# loud-esp-mini-rev-f-schematic_easyeda.net
KiCad netlist of a schematic drawn in EasyEDA
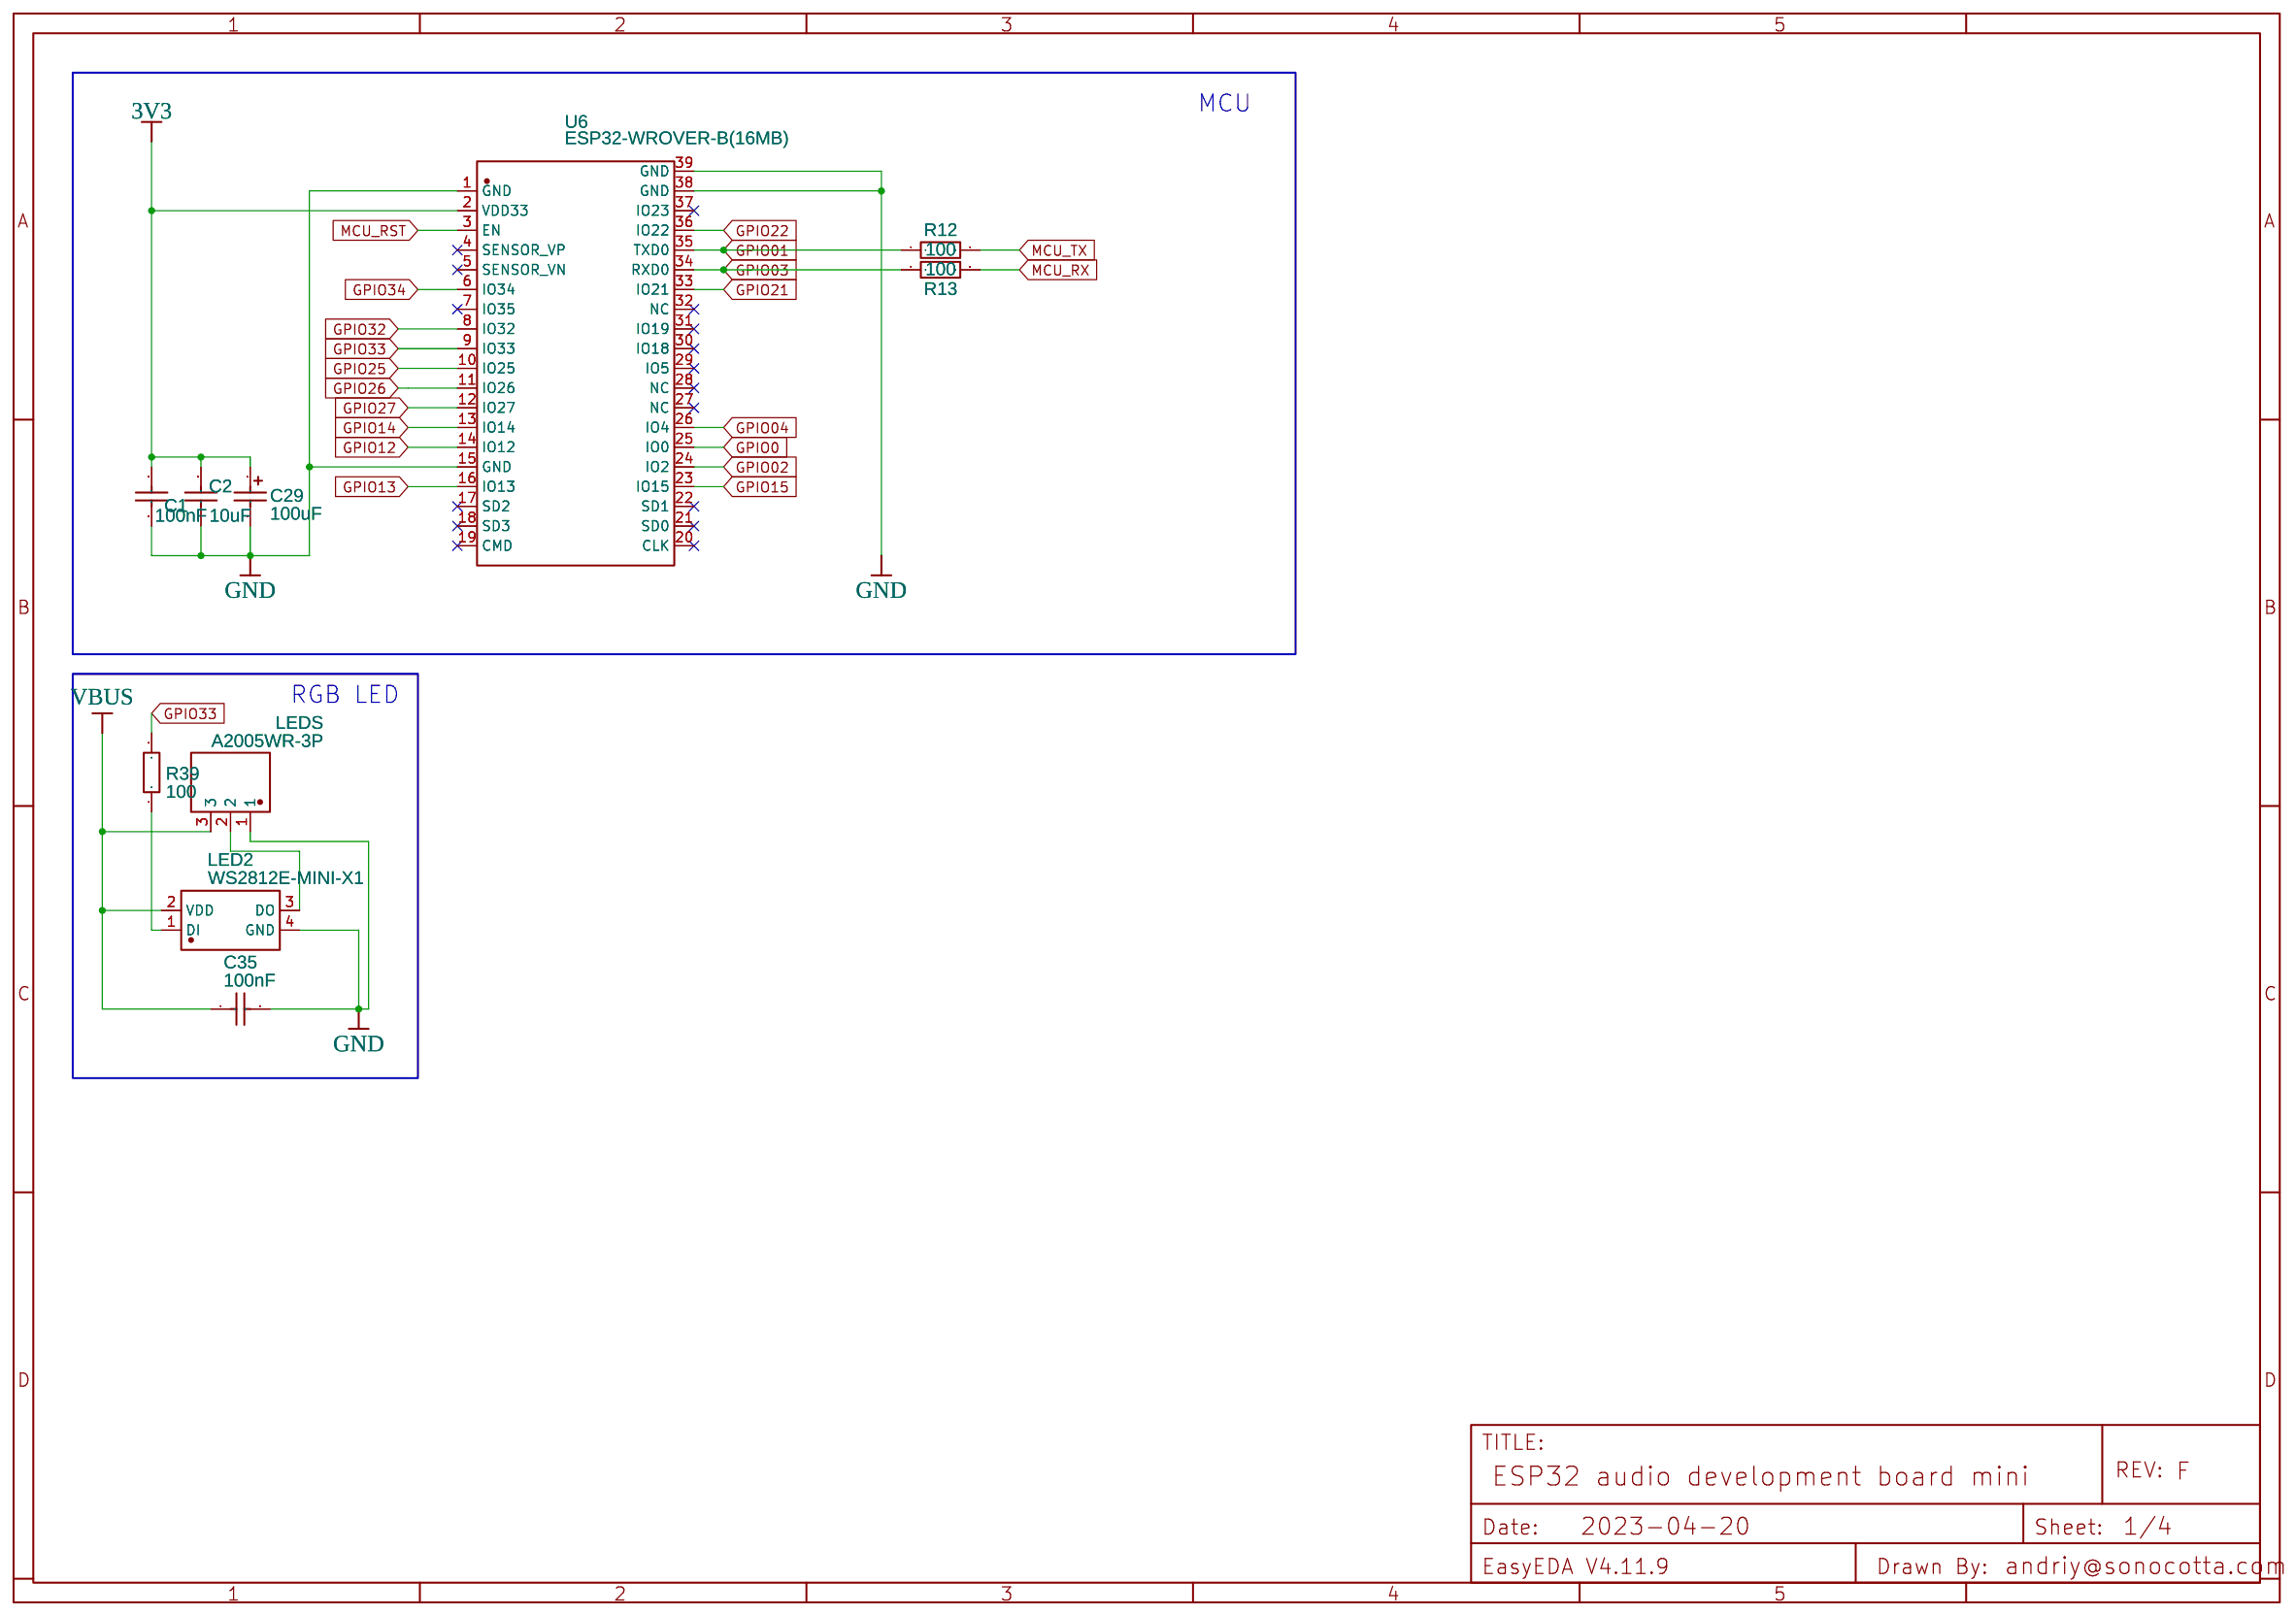
[diagram p0: MCU]
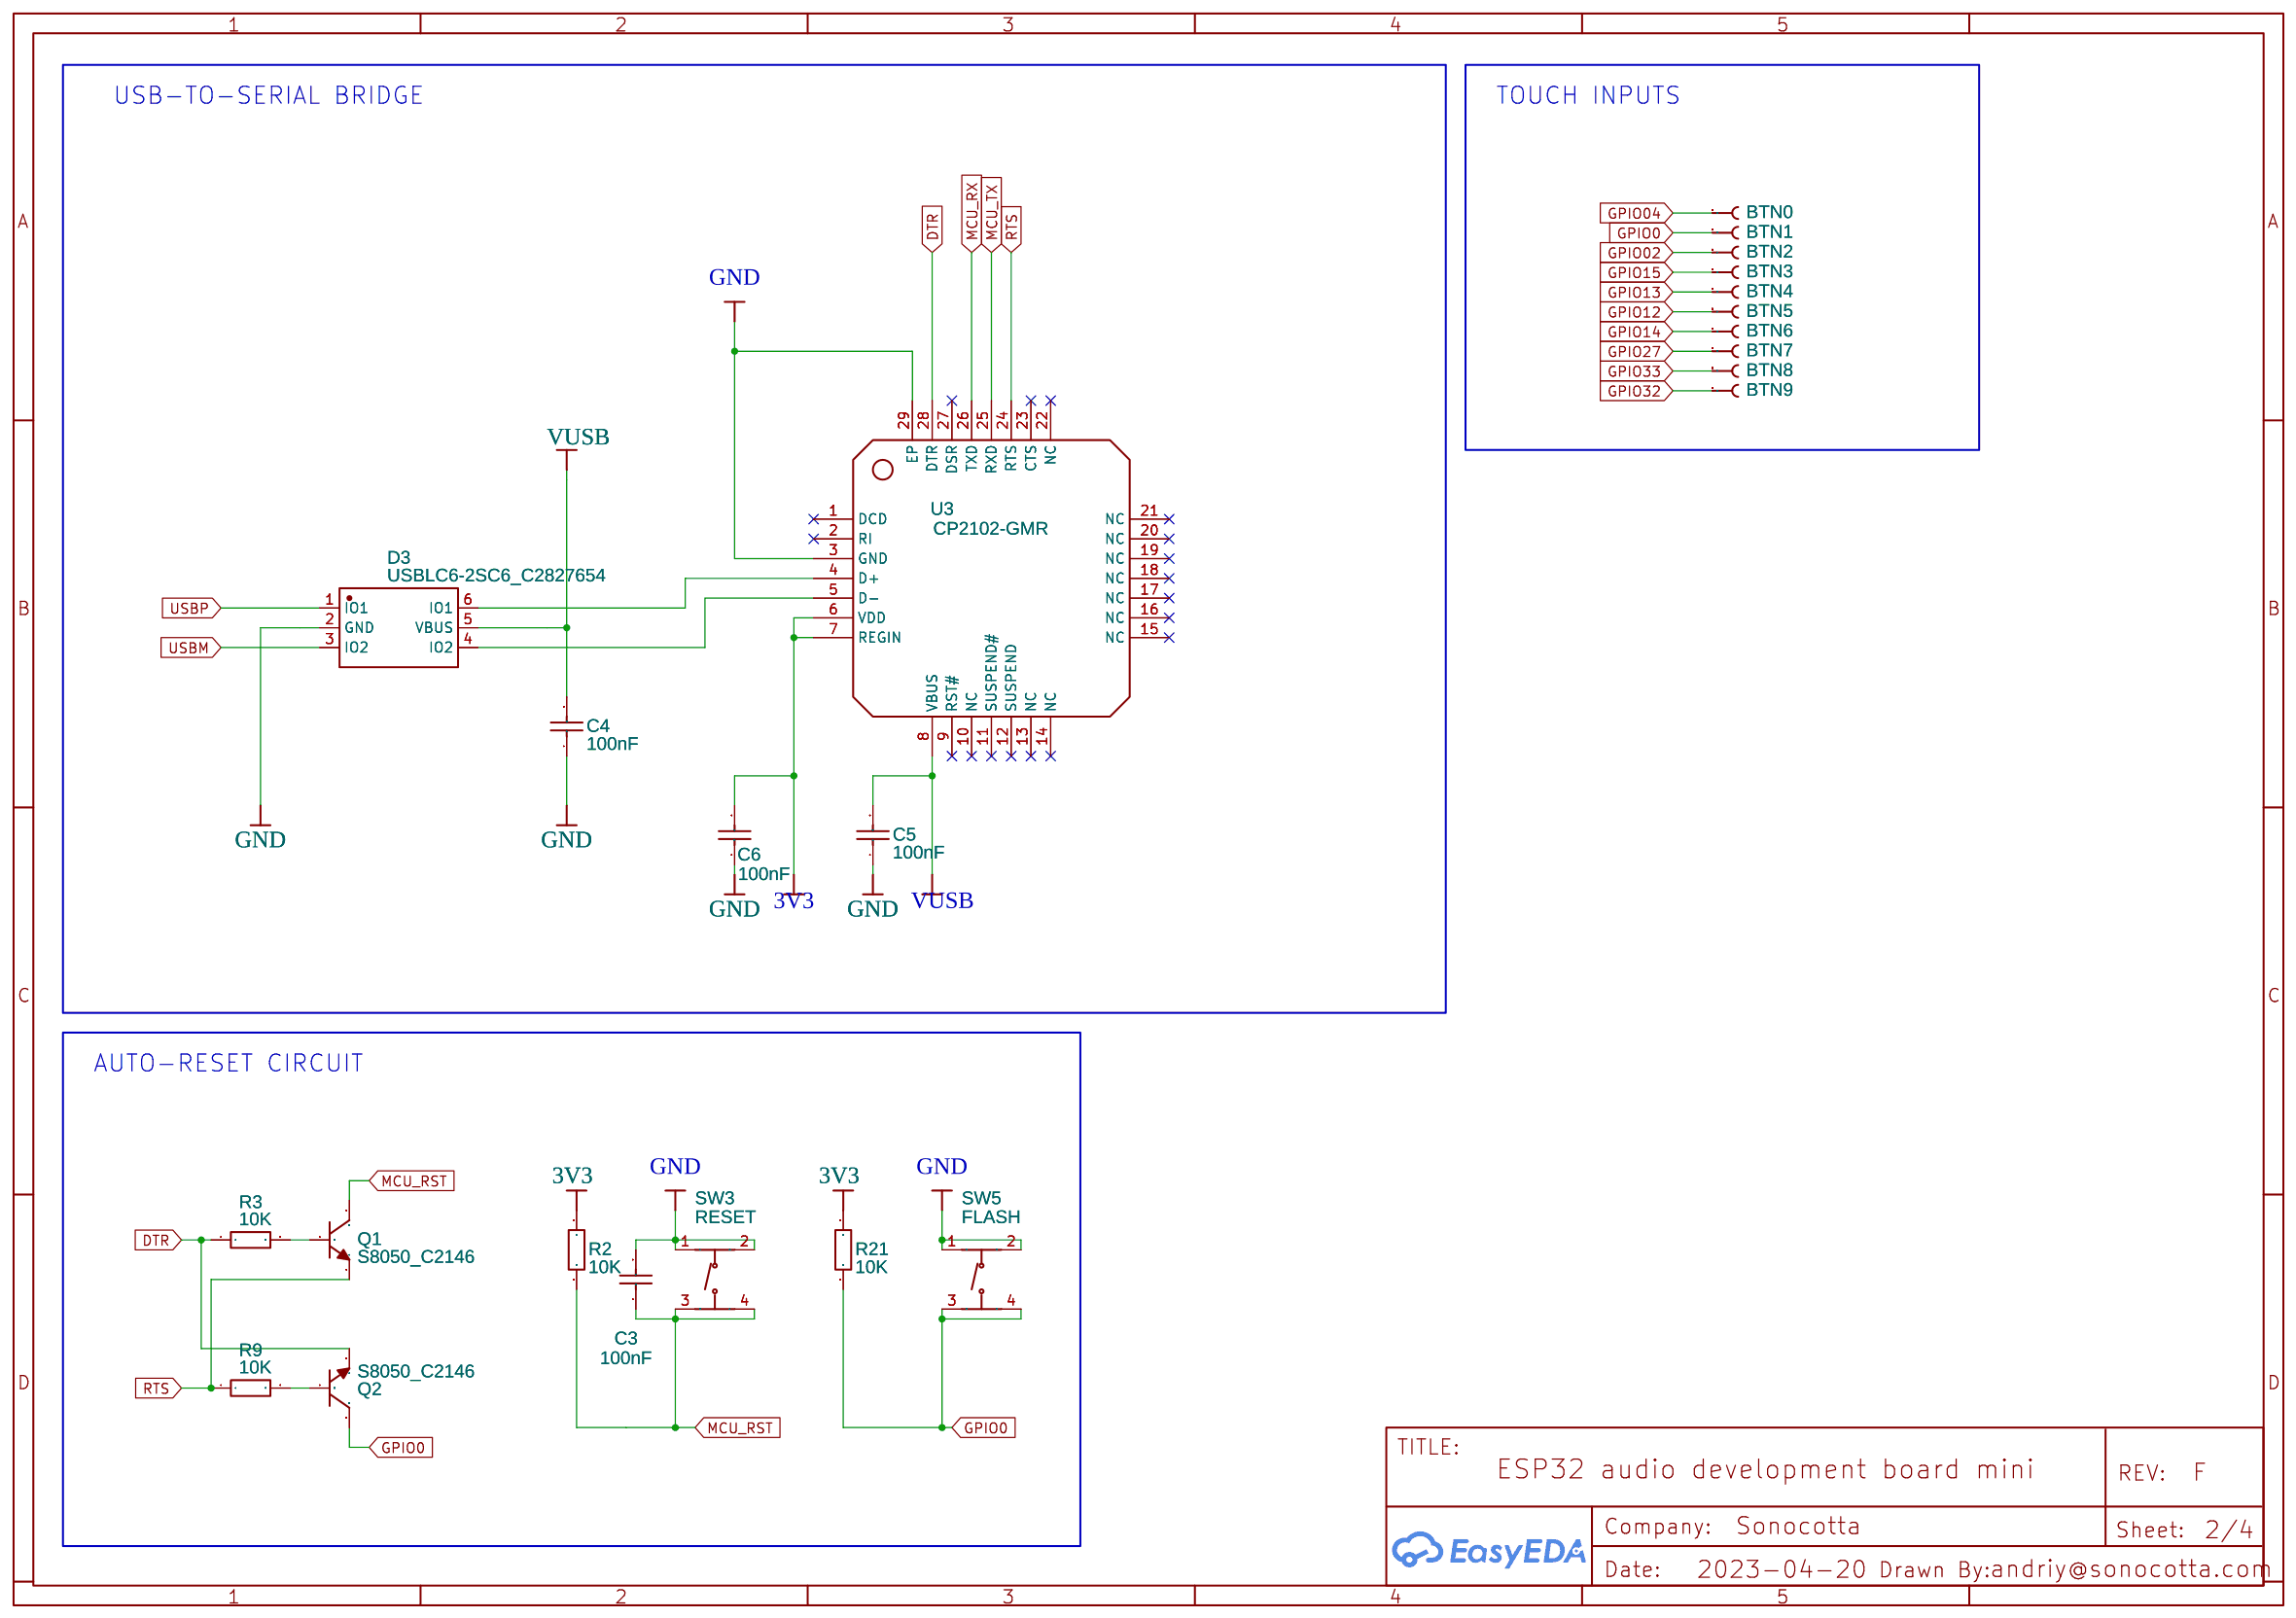
[diagram p1: SERIAL]
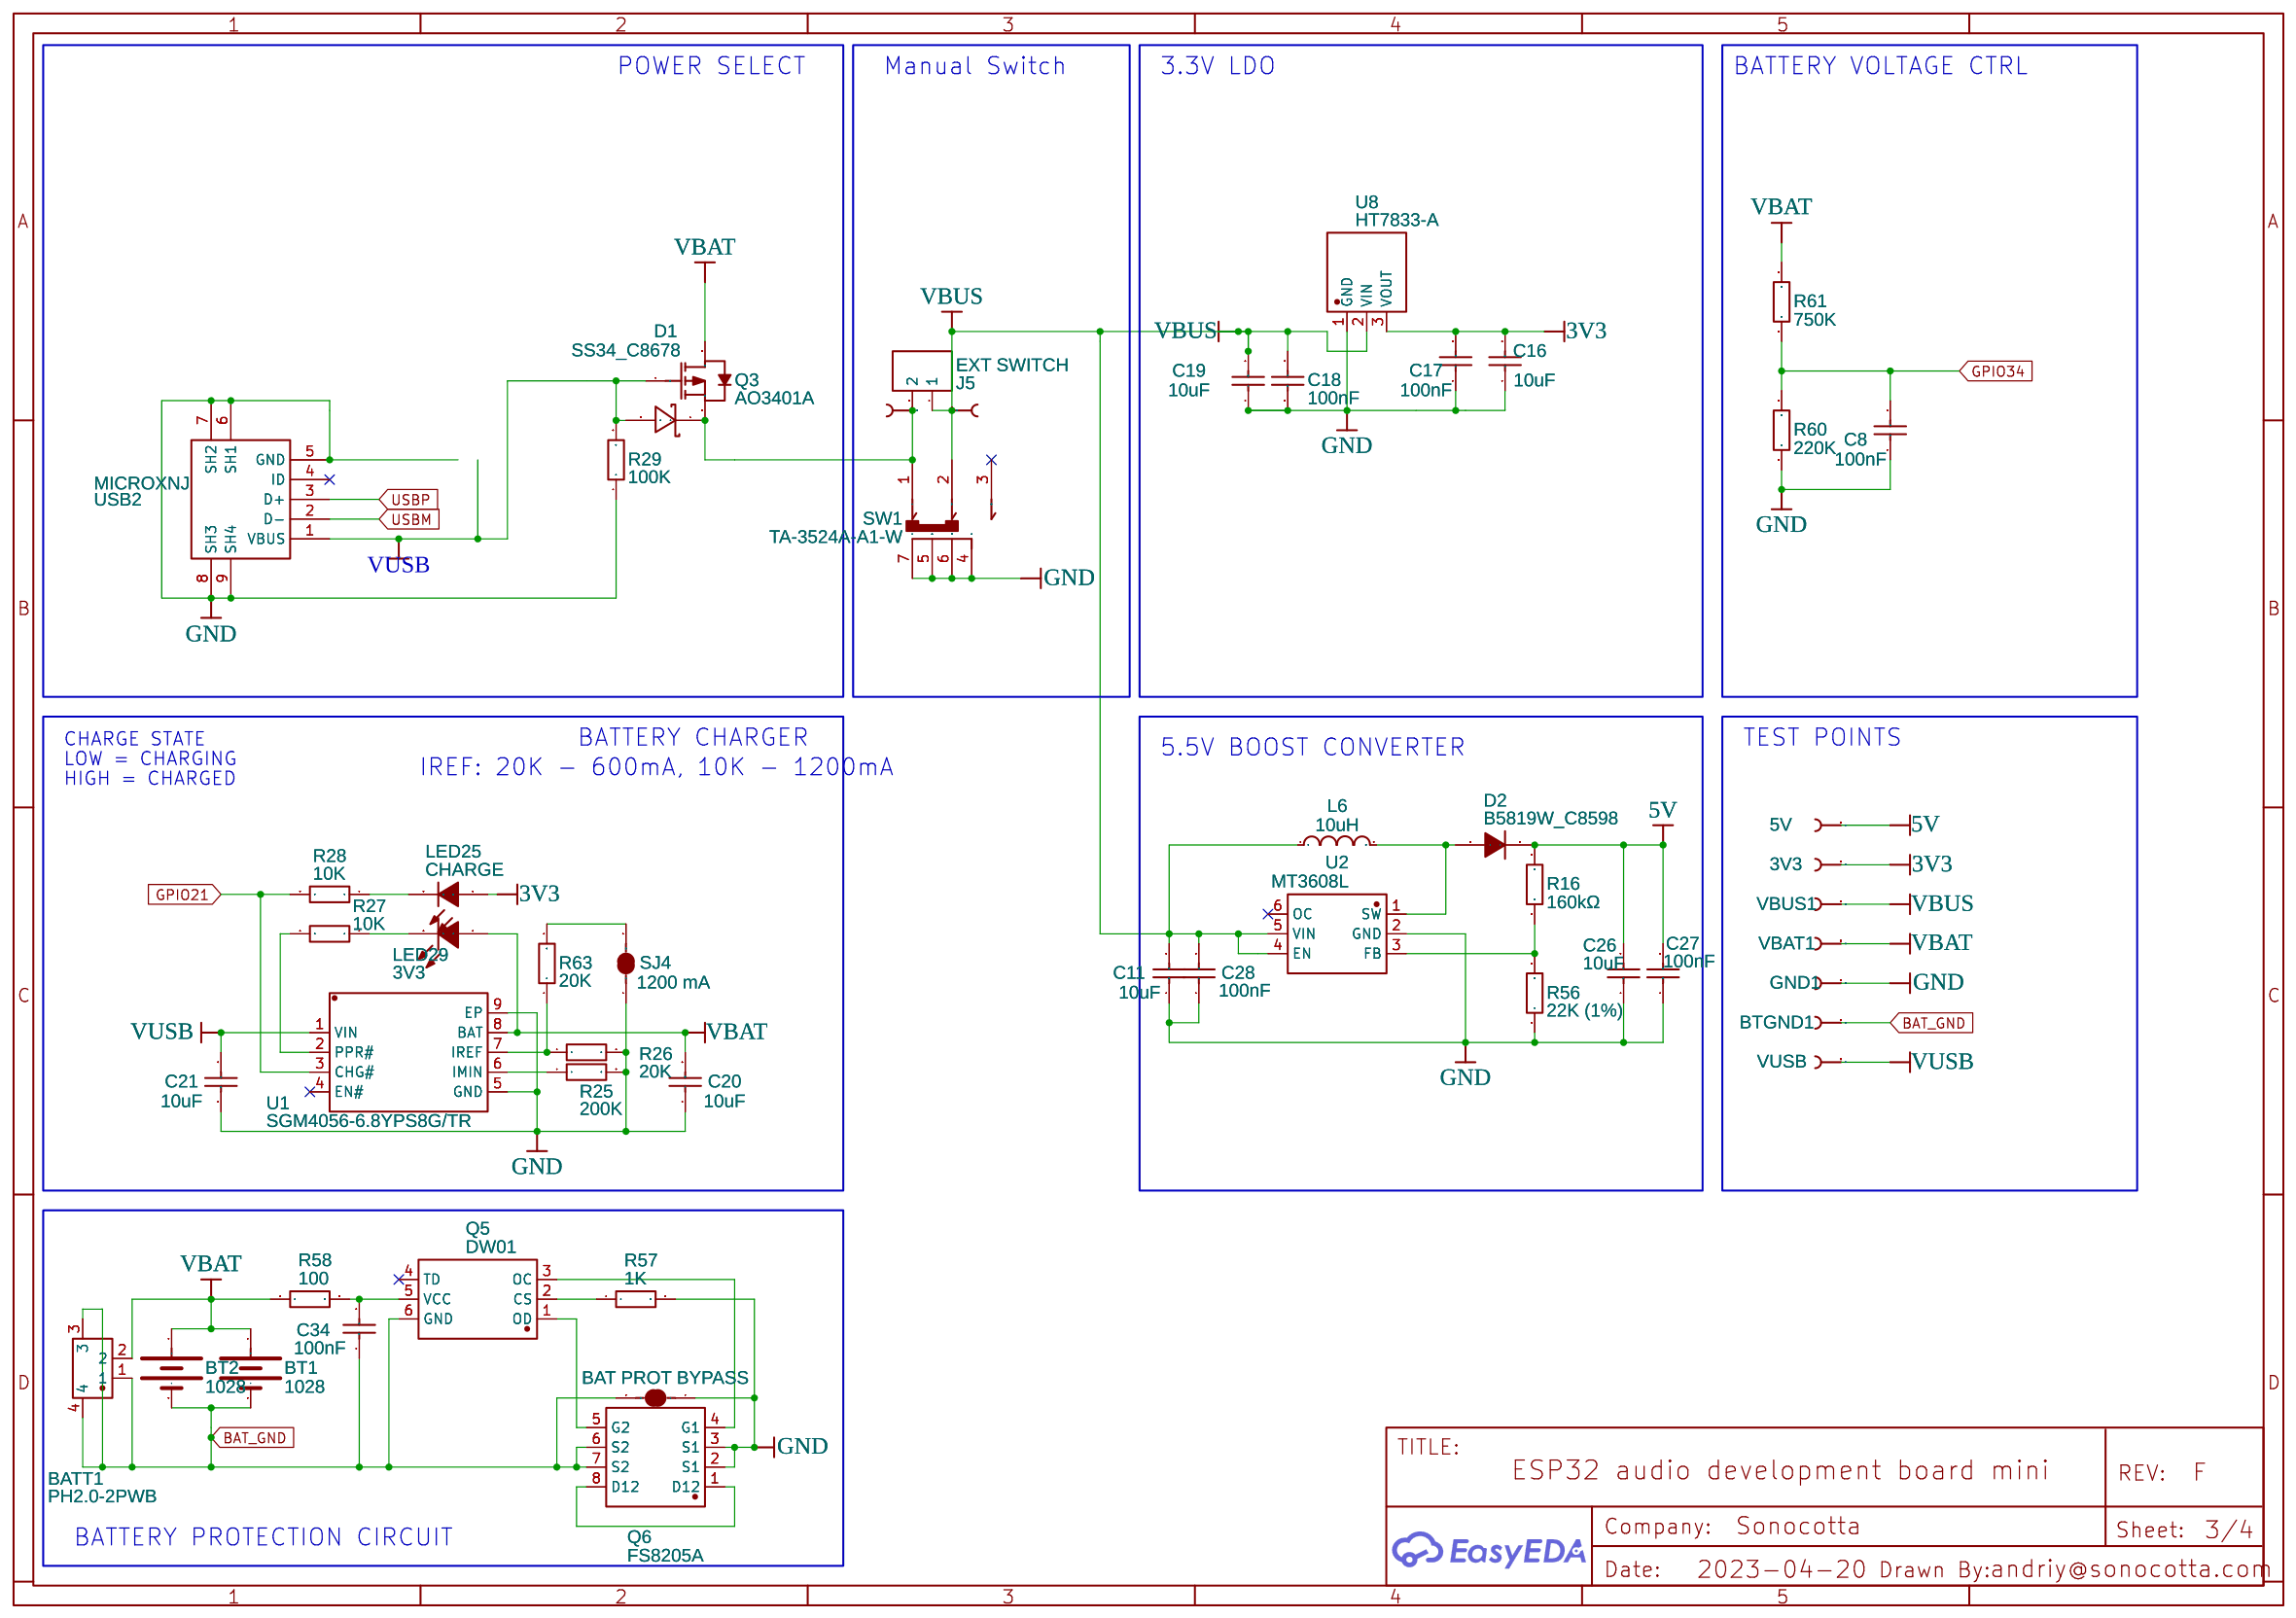
[diagram p2: POWER MGT]
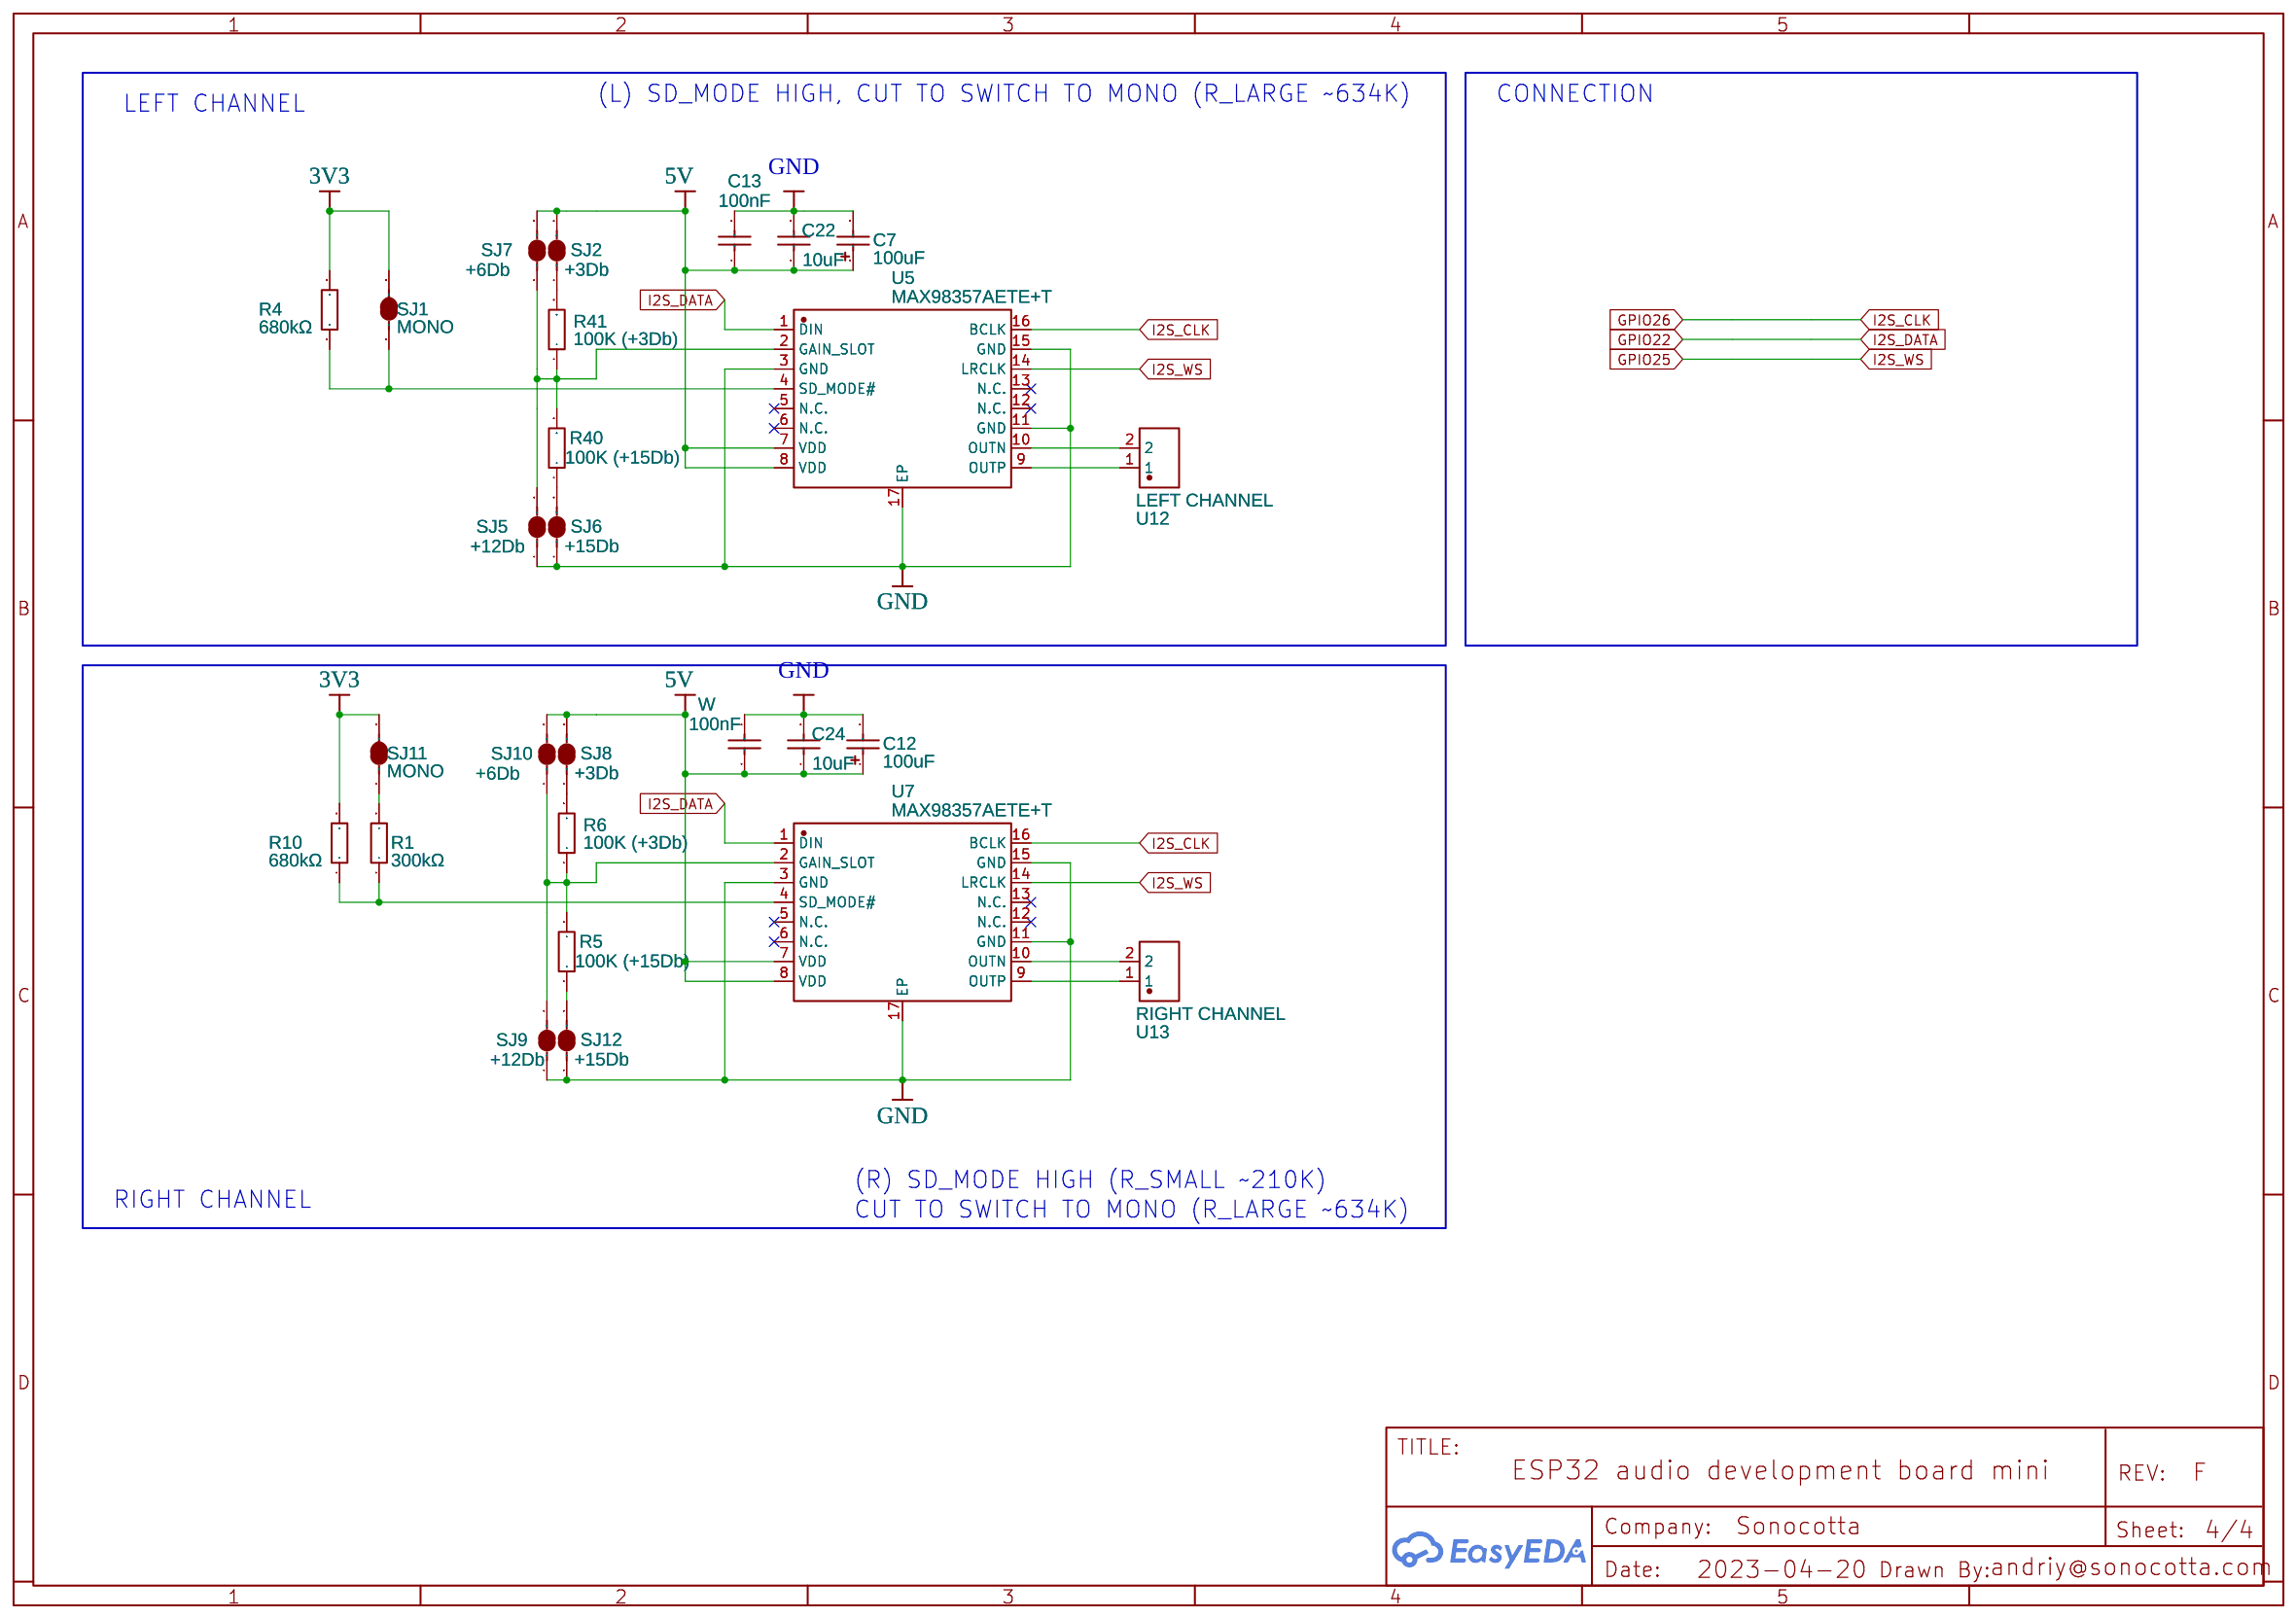
[diagram p3: DAC]

(export (version "E")
  (design (tool "Eeschema 10.0.6"))
  (components
    (comp (ref "C1")
      (value "100nF")
      (fields (field (name "Manufacturer Part") "CL05B104KO5NNNC") (field (name "Manufacturer") "SAMSUNG"))
      (libsource (lib "") (part "CL05B104KO5NNNC"))
    )
    (comp (ref "C2")
      (value "10uF")
      (fields (field (name "Manufacturer Part") "CL21A106KAYNNNE") (field (name "Manufacturer") "SAMSUNG"))
      (libsource (lib "") (part "CL21A106KAYNNNE"))
    )
    (comp (ref "C29")
      (value "100uF")
      (fields (field (name "Manufacturer Part") "TAJB107K006RNJ") (field (name "Manufacturer") "AVX"))
      (libsource (lib "") (part "TAJB107K006RNJ"))
    )
    (comp (ref "C35")
      (value "100nF")
      (fields (field (name "Manufacturer Part") "CL05B104KO5NNNC") (field (name "Manufacturer") "SAMSUNG"))
      (libsource (lib "") (part "C0201X6S104K6R3NTA"))
    )
    (comp (ref "LED2")
      (value "WS2812E-MINI-X1")
      (fields (field (name "Manufacturer") "worldsemi"))
      (libsource (lib "") (part "WS2812E-MINI-X1"))
    )
    (comp (ref "LEDS")
      (value "A2005WR-3P")
      (fields (field (name "Manufacturer") "Changjiang Connectors"))
      (libsource (lib "") (part "A2005WR-3P"))
    )
    (comp (ref "R12")
      (value "100")
      (fields (field (name "Manufacturer Part") "0402WGF1000TCE") (field (name "Manufacturer") "UniOhm"))
      (libsource (lib "") (part "0402WGF1000TCE_1"))
    )
    (comp (ref "R13")
      (value "100")
      (fields (field (name "Manufacturer Part") "0402WGF1000TCE") (field (name "Manufacturer") "UniOhm"))
      (libsource (lib "") (part "0402WGF1000TCE_1"))
    )
    (comp (ref "R39")
      (value "100")
      (fields (field (name "Manufacturer Part") "0402WGF1000TCE") (field (name "Manufacturer") "UniOhm"))
      (libsource (lib "") (part "0402WGF1000TCE"))
    )
    (comp (ref "U6")
      (value "ESP32-WROVER-B(16MB)")
      (fields (field (name "Manufacturer") "Espressif Systems"))
      (libsource (lib "") (part "ESP32-WROVER-B(16MB)"))
    )
    (comp (ref "BTN0") (value "SENSOR CAP 1") (libsource (lib "") (part "TEST-POINT2")))
    (comp (ref "BTN1") (value "SENSOR CAP 1") (libsource (lib "") (part "TEST-POINT2")))
    (comp (ref "BTN2") (value "SENSOR CAP 1") (libsource (lib "") (part "TEST-POINT2")))
    (comp (ref "BTN3") (value "SENSOR CAP 1") (libsource (lib "") (part "TEST-POINT2")))
    (comp (ref "BTN4") (value "SENSOR CAP 1") (libsource (lib "") (part "TEST-POINT2")))
    (comp (ref "BTN5") (value "SENSOR CAP 1") (libsource (lib "") (part "TEST-POINT2")))
    (comp (ref "BTN6") (value "SENSOR CAP 1") (libsource (lib "") (part "TEST-POINT2")))
    (comp (ref "BTN7") (value "SENSOR CAP 1") (libsource (lib "") (part "TEST-POINT2")))
    (comp (ref "BTN8") (value "SENSOR CAP 1") (libsource (lib "") (part "TEST-POINT2")))
    (comp (ref "BTN9") (value "SENSOR CAP 1") (libsource (lib "") (part "TEST-POINT2")))
    (comp (ref "C3")
      (value "100nF")
      (fields
        (field (name "BOM_Manufacturer Part") "CL05B104KO5NNNC")
        (field (name "BOM_Supplier Part") "C1525")
      )
      (libsource (lib "") (part "CL05B104KO5NNNC"))
    )
    (comp (ref "C4")
      (value "100nF")
      (fields
        (field (name "BOM_Manufacturer Part") "CL05B104KO5NNNC")
        (field (name "BOM_Supplier Part") "C1525")
      )
      (libsource (lib "") (part "CL05B104KO5NNNC"))
    )
    (comp (ref "C5")
      (value "100nF")
      (fields
        (field (name "BOM_Manufacturer Part") "CL05B104KO5NNNC")
        (field (name "BOM_Supplier Part") "C1525")
      )
      (libsource (lib "") (part "CL05B104KO5NNNC"))
    )
    (comp (ref "C6")
      (value "100nF")
      (fields
        (field (name "BOM_Manufacturer Part") "CL05B104KO5NNNC")
        (field (name "BOM_Supplier Part") "C1525")
      )
      (libsource (lib "") (part "CL05B104KO5NNNC"))
    )
    (comp (ref "D3")
      (value "USBLC6-2SC6_C2827654")
      (fields
        (field (name "BOM_Manufacturer Part") "USBLC6-2SC6")
        (field (name "BOM_Supplier Part") "C2827654")
      )
      (libsource (lib "") (part "USBLC6-2SC6_C2827654"))
    )
    (comp (ref "Q1")
      (value "S8050_C2146")
      (fields (field (name "BOM_Manufacturer Part") "S8050") (field (name "BOM_Supplier Part") "C2146"))
      (libsource (lib "") (part "S8050_C2146_1"))
    )
    (comp (ref "Q2")
      (value "S8050_C2146")
      (fields (field (name "BOM_Manufacturer Part") "S8050") (field (name "BOM_Supplier Part") "C2146"))
      (libsource (lib "") (part "S8050_C2146"))
    )
    (comp (ref "R2")
      (value "10K")
      (fields
        (field (name "BOM_Manufacturer Part") "0402WGF1002TCE")
        (field (name "BOM_Supplier Part") "C25744")
      )
      (libsource (lib "") (part "0402WGF1002TCE"))
    )
    (comp (ref "R3")
      (value "10K")
      (fields
        (field (name "BOM_Manufacturer Part") "0402WGF1002TCE")
        (field (name "BOM_Supplier Part") "C25744")
      )
      (libsource (lib "") (part "0402WGF1002TCE_1"))
    )
    (comp (ref "R9")
      (value "10K")
      (fields
        (field (name "BOM_Manufacturer Part") "0402WGF1002TCE")
        (field (name "BOM_Supplier Part") "C25744")
      )
      (libsource (lib "") (part "0402WGF1002TCE_1"))
    )
    (comp (ref "R21")
      (value "10K")
      (fields
        (field (name "BOM_Manufacturer Part") "0402WGF1002TCE")
        (field (name "BOM_Supplier Part") "C25744")
      )
      (libsource (lib "") (part "0402WGF1002TCE"))
    )
    (comp (ref "SW3")
      (value "RESET")
      (fields
        (field (name "BOM_Manufacturer Part") "TS-1187A-B-A-B")
        (field (name "BOM_Supplier Part") "C318884")
      )
      (libsource (lib "") (part "TS-1187A-B-A-B"))
    )
    (comp (ref "SW5")
      (value "FLASH")
      (fields
        (field (name "BOM_Manufacturer Part") "TS-1187A-B-A-B")
        (field (name "BOM_Supplier Part") "C318884")
      )
      (libsource (lib "") (part "TS-1187A-B-A-B"))
    )
    (comp (ref "U3")
      (value "CP2102-GMR")
      (fields (field (name "BOM_Supplier Part") "C6568"))
      (libsource (lib "") (part "CP2102-GMR"))
    )
    (comp (ref "3V3") (value "SENSOR CAP 1") (libsource (lib "") (part "TEST-POINT2_3")))
    (comp (ref "5V") (value "SENSOR CAP 1") (libsource (lib "") (part "TEST-POINT2_6")))
    (comp (ref "BATT1")
      (value "PH2.0-2PWB")
      (fields
        (field (name "BOM_Manufacturer Part") "PH2.0-2PWB Horizontal")
        (field (name "BOM_Supplier Part") "C47647")
      )
      (libsource (lib "") (part "PH2.0-2PWB"))
    )
    (comp (ref "BT1")
      (value "1028")
      (fields (field (name "BOM_Supplier Part") "C238063"))
      (libsource (lib "") (part "1028"))
    )
    (comp (ref "BT2")
      (value "1028")
      (fields (field (name "BOM_Supplier Part") "C238063"))
      (libsource (lib "") (part "1028"))
    )
    (comp (ref "BTGND1") (value "SENSOR CAP 1") (libsource (lib "") (part "TEST-POINT2_4")))
    (comp (ref "C8")
      (value "100nF")
      (fields
        (field (name "BOM_Manufacturer Part") "CL05B104KO5NNNC")
        (field (name "BOM_Supplier Part") "C1525")
      )
      (libsource (lib "") (part "CL05B104KO5NNNC"))
    )
    (comp (ref "C11")
      (value "10uF")
      (fields
        (field (name "BOM_Manufacturer Part") "CL21A106KAYNNNE")
        (field (name "BOM_Supplier Part") "C15850")
      )
      (libsource (lib "") (part "CL21A106KAYNNNE"))
    )
    (comp (ref "C16")
      (value "10uF")
      (fields
        (field (name "BOM_Manufacturer Part") "CL21A106KAYNNNE")
        (field (name "BOM_Supplier Part") "C15850")
      )
      (libsource (lib "") (part "CL21A106KAYNNNE"))
    )
    (comp (ref "C17")
      (value "100nF")
      (fields
        (field (name "BOM_Manufacturer Part") "CL05B104KO5NNNC")
        (field (name "BOM_Supplier Part") "C1525")
      )
      (libsource (lib "") (part "CL05B104KO5NNNC"))
    )
    (comp (ref "C18")
      (value "100nF")
      (fields
        (field (name "BOM_Manufacturer Part") "CL05B104KO5NNNC")
        (field (name "BOM_Supplier Part") "C1525")
      )
      (libsource (lib "") (part "CL05B104KO5NNNC"))
    )
    (comp (ref "C19")
      (value "10uF")
      (fields
        (field (name "BOM_Manufacturer Part") "CL21A106KAYNNNE")
        (field (name "BOM_Supplier Part") "C15850")
      )
      (libsource (lib "") (part "CL21A106KAYNNNE"))
    )
    (comp (ref "C20")
      (value "10uF")
      (fields
        (field (name "BOM_Manufacturer Part") "CL21A106KAYNNNE")
        (field (name "BOM_Supplier Part") "C15850")
      )
      (libsource (lib "") (part "CL21A106KAYNNNE"))
    )
    (comp (ref "C21")
      (value "10uF")
      (fields
        (field (name "BOM_Manufacturer Part") "CL21A106KAYNNNE")
        (field (name "BOM_Supplier Part") "C15850")
      )
      (libsource (lib "") (part "CL21A106KAYNNNE"))
    )
    (comp (ref "C26")
      (value "10uF")
      (fields
        (field (name "BOM_Manufacturer Part") "CL21A106KAYNNNE")
        (field (name "BOM_Supplier Part") "C15850")
      )
      (libsource (lib "") (part "CL21A106KAYNNNE"))
    )
    (comp (ref "C27")
      (value "100nF")
      (fields
        (field (name "BOM_Manufacturer Part") "CL05B104KO5NNNC")
        (field (name "BOM_Supplier Part") "C1525")
      )
      (libsource (lib "") (part "CL05B104KO5NNNC"))
    )
    (comp (ref "C28")
      (value "100nF")
      (fields
        (field (name "BOM_Manufacturer Part") "CL05B104KO5NNNC")
        (field (name "BOM_Supplier Part") "C1525")
      )
      (libsource (lib "") (part "CL05B104KO5NNNC"))
    )
    (comp (ref "C34")
      (value "100nF")
      (fields
        (field (name "BOM_Manufacturer Part") "CL05B104KO5NNNC")
        (field (name "BOM_Supplier Part") "C1525")
      )
      (libsource (lib "") (part "CL05B104KO5NNNC"))
    )
    (comp (ref "D1")
      (value "SS34_C8678")
      (fields (field (name "BOM_Manufacturer Part") "SS34") (field (name "BOM_Supplier Part") "C8678"))
      (libsource (lib "") (part "SS34_C8678"))
    )
    (comp (ref "D2")
      (value "B5819W_C8598")
      (fields (field (name "BOM_Manufacturer Part") "B5819W") (field (name "BOM_Supplier Part") "C8598"))
      (libsource (lib "") (part "B5819W_C8598"))
    )
    (comp (ref "EXT_SW_1") (value "SENSOR CAP 1") (libsource (lib "") (part "TEST-POINT2_7")))
    (comp (ref "EXT_SW_2") (value "SENSOR CAP 1") (libsource (lib "") (part "TEST-POINT2")))
    (comp (ref "GND1") (value "SENSOR CAP 1") (libsource (lib "") (part "TEST-POINT2_1")))
    (comp (ref "J5")
      (value "EXT SWITCH")
      (fields (field (name "BOM_Supplier Part") "C124375"))
      (libsource (lib "") (part "HDR-M-2.54_1x2"))
    )
    (comp (ref "L6")
      (value "10uH")
      (fields
        (field (name "BOM_Manufacturer Part") "FXL0630-100-M")
        (field (name "BOM_Supplier Part") "C167223")
      )
      (libsource (lib "") (part "FXL0630-100-M"))
    )
    (comp (ref "LED25")
      (value "CHARGE")
      (fields
        (field (name "BOM_Manufacturer Part") "19-217/GHC-YR1S2/3T")
        (field (name "BOM_Supplier Part") "C72043")
      )
      (libsource (lib "") (part "19-217/GHC-YR1S2/3T"))
    )
    (comp (ref "LED29")
      (value "3V3")
      (fields (field (name "BOM_Manufacturer Part") "KT-0603R") (field (name "BOM_Supplier Part") "C2286"))
      (libsource (lib "") (part "KT-0603R"))
    )
    (comp (ref "Q3")
      (value "AO3401A")
      (fields (field (name "BOM_Supplier Part") "C15127"))
      (libsource (lib "") (part "AO3401A"))
    )
    (comp (ref "Q5")
      (value "DW01")
      (fields (field (name "BOM_Supplier Part") "C181096"))
      (libsource (lib "") (part "DW01"))
    )
    (comp (ref "Q6")
      (value "FS8205A")
      (fields (field (name "BOM_Supplier Part") "C16052"))
      (libsource (lib "") (part "FS8205A"))
    )
    (comp (ref "R16")
      (value "160kΩ")
      (fields
        (field (name "BOM_Manufacturer Part") "0603WAF1603T5E")
        (field (name "BOM_Supplier Part") "C22813")
      )
      (libsource (lib "") (part "0603WAF1603T5E"))
    )
    (comp (ref "R25")
      (value "200K")
      (fields
        (field (name "BOM_Manufacturer Part") "0402WGF2003TCE")
        (field (name "BOM_Supplier Part") "C25764")
      )
      (libsource (lib "") (part "0402WGF2003TCE"))
    )
    (comp (ref "R26")
      (value "20K")
      (fields
        (field (name "BOM_Manufacturer Part") "0402WGF2002TCE")
        (field (name "BOM_Supplier Part") "C25765")
      )
      (libsource (lib "") (part "0402WGF2002TCE_1"))
    )
    (comp (ref "R27")
      (value "10K")
      (fields
        (field (name "BOM_Manufacturer Part") "0402WGF1002TCE")
        (field (name "BOM_Supplier Part") "C25744")
      )
      (libsource (lib "") (part "0402WGF1002TCE"))
    )
    (comp (ref "R28")
      (value "10K")
      (fields
        (field (name "BOM_Manufacturer Part") "0402WGF1002TCE")
        (field (name "BOM_Supplier Part") "C25744")
      )
      (libsource (lib "") (part "0402WGF1002TCE"))
    )
    (comp (ref "R29")
      (value "100K")
      (fields
        (field (name "BOM_Manufacturer Part") "0402WGF1003TCE")
        (field (name "BOM_Supplier Part") "C25741")
      )
      (libsource (lib "") (part "0402WGF1003TCE"))
    )
    (comp (ref "R56")
      (value "22K (1%)")
      (fields
        (field (name "BOM_Manufacturer Part") "0603WAF2202T5E")
        (field (name "BOM_Supplier Part") "C31850")
      )
      (libsource (lib "") (part "0603WAF2202T5E"))
    )
    (comp (ref "R57")
      (value "1K")
      (fields
        (field (name "BOM_Manufacturer Part") "0402WGF1001TCE")
        (field (name "BOM_Supplier Part") "C11702")
      )
      (libsource (lib "") (part "0402WGF1001TCE"))
    )
    (comp (ref "R58")
      (value "100")
      (fields
        (field (name "BOM_Manufacturer Part") "0402WGF1000TCE")
        (field (name "BOM_Supplier Part") "C25076")
      )
      (libsource (lib "") (part "0402WGF1000TCE"))
    )
    (comp (ref "R60")
      (value "220K")
      (fields
        (field (name "BOM_Manufacturer Part") "0603WAF2203T5E")
        (field (name "BOM_Supplier Part") "C22961")
      )
      (libsource (lib "") (part "0603WAF2203T5E"))
    )
    (comp (ref "R61")
      (value "750K")
      (fields
        (field (name "BOM_Manufacturer Part") "0603WAF7503T5E")
        (field (name "BOM_Supplier Part") "C23240")
      )
      (libsource (lib "") (part "0603WAF7503T5E"))
    )
    (comp (ref "R63")
      (value "20K")
      (fields
        (field (name "BOM_Manufacturer Part") "0402WGF2002TCE")
        (field (name "BOM_Supplier Part") "C25765")
      )
      (libsource (lib "") (part "0402WGF2002TCE"))
    )
    (comp (ref "SJ3") (value "BAT PROT BYPASS") (libsource (lib "") (part "JUMPER-PAD-2-NO")))
    (comp (ref "SJ4") (value "1200 mA") (libsource (lib "") (part "JUMPER-PAD-2-NO_1")))
    (comp (ref "SW1")
      (value "TA-3524A-A1-W")
      (fields (field (name "BOM_Supplier Part") "C730329"))
      (libsource (lib "") (part "TA-3524A-A1-W"))
    )
    (comp (ref "U1")
      (value "SGM4056-6.8YPS8G/TR")
      (fields (field (name "BOM_Supplier Part") "C79687"))
      (libsource (lib "") (part "SGM4056-6.8YPS8G/TR"))
    )
    (comp (ref "U2")
      (value "MT3608L")
      (fields (field (name "BOM_Supplier Part") "C2932326"))
      (libsource (lib "") (part "MT3608L"))
    )
    (comp (ref "U8")
      (value "HT7833-A")
      (fields (field (name "BOM_Supplier Part") "C347195"))
      (libsource (lib "") (part "HT7833-A"))
    )
    (comp (ref "USB2")
      (value "MICROXNJ")
      (fields (field (name "BOM_Manufacturer Part") "MicroXNJ") (field (name "BOM_Supplier Part") "C404969"))
      (libsource (lib "") (part "MICROXNJ"))
    )
    (comp (ref "VBAT1") (value "SENSOR CAP 1") (libsource (lib "") (part "TEST-POINT2_2")))
    (comp (ref "VBUS1") (value "SENSOR CAP 1") (libsource (lib "") (part "TEST-POINT2_8")))
    (comp (ref "VUSB") (value "SENSOR CAP 1") (libsource (lib "") (part "TEST-POINT2_5")))
    (comp (ref "C7")
      (value "100uF")
      (fields
        (field (name "BOM_Manufacturer Part") "TAJB107K006RNJ")
        (field (name "BOM_Supplier Part") "C16133")
      )
      (libsource (lib "") (part "TAJB107K006RNJ"))
    )
    (comp (ref "C12")
      (value "100uF")
      (fields
        (field (name "BOM_Manufacturer Part") "TAJB107K006RNJ")
        (field (name "BOM_Supplier Part") "C16133")
      )
      (libsource (lib "") (part "TAJB107K006RNJ"))
    )
    (comp (ref "C13")
      (value "100nF")
      (fields
        (field (name "BOM_Manufacturer Part") "CL05B104KO5NNNC")
        (field (name "BOM_Supplier Part") "C1525")
      )
      (libsource (lib "") (part "CL05B104KO5NNNC"))
    )
    (comp (ref "C22")
      (value "10uF")
      (fields
        (field (name "BOM_Manufacturer Part") "CL21A106KAYNNNE")
        (field (name "BOM_Supplier Part") "C15850")
      )
      (libsource (lib "") (part "CL21A106KAYNNNE"))
    )
    (comp (ref "C24")
      (value "10uF")
      (fields
        (field (name "BOM_Manufacturer Part") "CL21A106KAYNNNE")
        (field (name "BOM_Supplier Part") "C15850")
      )
      (libsource (lib "") (part "CL21A106KAYNNNE"))
    )
    (comp (ref "R1")
      (value "300kΩ")
      (fields
        (field (name "BOM_Manufacturer Part") "0402WGF3003TCE")
        (field (name "BOM_Supplier Part") "C25774")
      )
      (libsource (lib "") (part "0402WGF3003TCE"))
    )
    (comp (ref "R4")
      (value "680kΩ")
      (fields
        (field (name "BOM_Manufacturer Part") "0603WAF6803T5E")
        (field (name "BOM_Supplier Part") "C25822")
      )
      (libsource (lib "") (part "0603WAF6803T5E"))
    )
    (comp (ref "R5")
      (value "100K (+15Db)")
      (fields
        (field (name "BOM_Manufacturer Part") "0402WGF1003TCE")
        (field (name "BOM_Supplier Part") "C25741")
      )
      (libsource (lib "") (part "0402WGF1003TCE"))
    )
    (comp (ref "R6")
      (value "100K (+3Db)")
      (fields
        (field (name "BOM_Manufacturer Part") "0402WGF1003TCE")
        (field (name "BOM_Supplier Part") "C25741")
      )
      (libsource (lib "") (part "0402WGF1003TCE"))
    )
    (comp (ref "R10")
      (value "680kΩ")
      (fields
        (field (name "BOM_Manufacturer Part") "0603WAF6803T5E")
        (field (name "BOM_Supplier Part") "C25822")
      )
      (libsource (lib "") (part "0603WAF6803T5E"))
    )
    (comp (ref "R40")
      (value "100K (+15Db)")
      (fields
        (field (name "BOM_Manufacturer Part") "0402WGF1003TCE")
        (field (name "BOM_Supplier Part") "C25741")
      )
      (libsource (lib "") (part "0402WGF1003TCE"))
    )
    (comp (ref "R41")
      (value "100K (+3Db)")
      (fields
        (field (name "BOM_Manufacturer Part") "0402WGF1003TCE")
        (field (name "BOM_Supplier Part") "C25741")
      )
      (libsource (lib "") (part "0402WGF1003TCE"))
    )
    (comp (ref "SJ1") (value "MONO") (libsource (lib "") (part "JUMPER-PAD-2-NC_BY_TRACENO_SILK")))
    (comp (ref "SJ2") (value "+3Db") (libsource (lib "") (part "JUMPER-PAD-2-NO")))
    (comp (ref "SJ5") (value "+12Db") (libsource (lib "") (part "JUMPER-PAD-2-NO")))
    (comp (ref "SJ6") (value "+15Db") (libsource (lib "") (part "JUMPER-PAD-2-NO")))
    (comp (ref "SJ7") (value "+6Db") (libsource (lib "") (part "JUMPER-PAD-2-NO")))
    (comp (ref "SJ8") (value "+3Db") (libsource (lib "") (part "JUMPER-PAD-2-NO")))
    (comp (ref "SJ9") (value "+12Db") (libsource (lib "") (part "JUMPER-PAD-2-NO")))
    (comp (ref "SJ10") (value "+6Db") (libsource (lib "") (part "JUMPER-PAD-2-NO")))
    (comp (ref "SJ11") (value "MONO") (libsource (lib "") (part "JUMPER-PAD-2-NC_BY_TRACENO_SILK")))
    (comp (ref "SJ12") (value "+15Db") (libsource (lib "") (part "JUMPER-PAD-2-NO")))
    (comp (ref "U5")
      (value "MAX98357AETE+T")
      (fields (field (name "BOM_Supplier Part") "C910544"))
      (libsource (lib "") (part "MAX98357AETE+T"))
    )
    (comp (ref "U7")
      (value "MAX98357AETE+T")
      (fields (field (name "BOM_Supplier Part") "C910544"))
      (libsource (lib "") (part "MAX98357AETE+T"))
    )
    (comp (ref "U12")
      (value "LEFT CHANNEL")
      (fields
        (field (name "BOM_Manufacturer Part") "KF350-3.5-2P")
        (field (name "BOM_Supplier Part") "C474892")
      )
      (libsource (lib "") (part "KF350-3.5-2P"))
    )
    (comp (ref "U13")
      (value "RIGHT CHANNEL")
      (fields
        (field (name "BOM_Manufacturer Part") "KF350-3.5-2P")
        (field (name "BOM_Supplier Part") "C474892")
      )
      (libsource (lib "") (part "KF350-3.5-2P"))
    )
    (comp (ref "W")
      (value "100nF")
      (fields
        (field (name "BOM_Manufacturer Part") "CL05B104KO5NNNC")
        (field (name "BOM_Supplier Part") "C1525")
      )
      (libsource (lib "") (part "CL05B104KO5NNNC_1"))
    )
  )
  (nets
    (net (code "1") (name "3V3") (class "Default")
      (node (ref "3V3") (pin "P$1") (pinfunction "1_P$1") (pintype "unspecified"))
      (node (ref "C1") (pin "2") (pinfunction "2_2") (pintype "input"))
      (node (ref "C16") (pin "2") (pinfunction "2_2") (pintype "input"))
      (node (ref "C17") (pin "2") (pinfunction "2_2") (pintype "input"))
      (node (ref "C2") (pin "2") (pinfunction "2_2") (pintype "input"))
      (node (ref "C29") (pin "1") (pinfunction "1_1") (pintype "input"))
      (node (ref "C6") (pin "2") (pinfunction "2_2") (pintype "input"))
      (node (ref "LED25") (pin "1") (pinfunction "A_1") (pintype "input"))
      (node (ref "R10") (pin "2") (pinfunction "2_2") (pintype "input"))
      (node (ref "R2") (pin "1") (pinfunction "1_1") (pintype "input"))
      (node (ref "R21") (pin "1") (pinfunction "1_1") (pintype "input"))
      (node (ref "R4") (pin "2") (pinfunction "2_2") (pintype "input"))
      (node (ref "SJ1") (pin "2") (pinfunction "2_2") (pintype "unspecified"))
      (node (ref "SJ11") (pin "2") (pinfunction "2_2") (pintype "unspecified"))
      (node (ref "U3") (pin "6") (pinfunction "VDD_6") (pintype "unspecified"))
      (node (ref "U3") (pin "7") (pinfunction "REGIN_7") (pintype "unspecified"))
      (node (ref "U6") (pin "2") (pinfunction "VDD33_2") (pintype "unspecified"))
      (node (ref "U8") (pin "3") (pinfunction "VOUT_3") (pintype "unspecified"))
    )
    (net (code "2") (name "5V") (class "Default")
      (node (ref "5V") (pin "P$1") (pinfunction "1_P$1") (pintype "unspecified"))
      (node (ref "C12") (pin "1") (pinfunction "1_1") (pintype "input"))
      (node (ref "C13") (pin "1") (pinfunction "1_1") (pintype "input"))
      (node (ref "C22") (pin "1") (pinfunction "1_1") (pintype "input"))
      (node (ref "C24") (pin "1") (pinfunction "1_1") (pintype "input"))
      (node (ref "C26") (pin "2") (pinfunction "2_2") (pintype "input"))
      (node (ref "C27") (pin "2") (pinfunction "2_2") (pintype "input"))
      (node (ref "C7") (pin "1") (pinfunction "1_1") (pintype "input"))
      (node (ref "D2") (pin "1") (pinfunction "-_1") (pintype "unspecified"))
      (node (ref "R16") (pin "2") (pinfunction "2_2") (pintype "input"))
      (node (ref "SJ10") (pin "2") (pinfunction "2_2") (pintype "unspecified"))
      (node (ref "SJ2") (pin "2") (pinfunction "2_2") (pintype "unspecified"))
      (node (ref "SJ7") (pin "2") (pinfunction "2_2") (pintype "unspecified"))
      (node (ref "SJ8") (pin "2") (pinfunction "2_2") (pintype "unspecified"))
      (node (ref "U5") (pin "7") (pinfunction "VDD_7") (pintype "unspecified"))
      (node (ref "U5") (pin "8") (pinfunction "VDD_8") (pintype "unspecified"))
      (node (ref "U7") (pin "7") (pinfunction "VDD_7") (pintype "unspecified"))
      (node (ref "U7") (pin "8") (pinfunction "VDD_8") (pintype "unspecified"))
      (node (ref "W") (pin "1") (pinfunction "1_1") (pintype "input"))
    )
    (net (code "3") (name "BAT_GND") (class "Default")
      (node (ref "BATT1") (pin "1") (pinfunction "1_1") (pintype "unspecified"))
      (node (ref "BATT1") (pin "3") (pinfunction "3_3") (pintype "unspecified"))
      (node (ref "BATT1") (pin "4") (pinfunction "4_4") (pintype "unspecified"))
      (node (ref "BT1") (pin "2") (pinfunction "-_2") (pintype "passive"))
      (node (ref "BT2") (pin "2") (pinfunction "-_2") (pintype "passive"))
      (node (ref "BTGND1") (pin "P$1") (pinfunction "1_P$1") (pintype "unspecified"))
      (node (ref "C34") (pin "1") (pinfunction "1_1") (pintype "input"))
      (node (ref "Q5") (pin "6") (pinfunction "GND_6") (pintype "unspecified"))
      (node (ref "Q6") (pin "6") (pinfunction "S2_6") (pintype "unspecified"))
      (node (ref "Q6") (pin "7") (pinfunction "S2_7") (pintype "unspecified"))
      (node (ref "SJ3") (pin "2") (pinfunction "2_2") (pintype "unspecified"))
    )
    (net (code "4") (name "DTR") (class "Default")
      (node (ref "Q2") (pin "2") (pinfunction "E_2") (pintype "unspecified"))
      (node (ref "R3") (pin "1") (pinfunction "1_1") (pintype "input"))
      (node (ref "U3") (pin "28") (pinfunction "DTR_28") (pintype "unspecified"))
    )
    (net (code "5") (name "GND") (class "Default")
      (node (ref "C1") (pin "1") (pinfunction "1_1") (pintype "input"))
      (node (ref "C11") (pin "1") (pinfunction "1_1") (pintype "input"))
      (node (ref "C12") (pin "2") (pinfunction "2_2") (pintype "input"))
      (node (ref "C13") (pin "2") (pinfunction "2_2") (pintype "input"))
      (node (ref "C16") (pin "1") (pinfunction "1_1") (pintype "input"))
      (node (ref "C17") (pin "1") (pinfunction "1_1") (pintype "input"))
      (node (ref "C18") (pin "1") (pinfunction "1_1") (pintype "input"))
      (node (ref "C19") (pin "1") (pinfunction "1_1") (pintype "input"))
      (node (ref "C2") (pin "1") (pinfunction "1_1") (pintype "input"))
      (node (ref "C20") (pin "1") (pinfunction "1_1") (pintype "input"))
      (node (ref "C21") (pin "1") (pinfunction "1_1") (pintype "input"))
      (node (ref "C22") (pin "2") (pinfunction "2_2") (pintype "input"))
      (node (ref "C24") (pin "2") (pinfunction "2_2") (pintype "input"))
      (node (ref "C26") (pin "1") (pinfunction "1_1") (pintype "input"))
      (node (ref "C27") (pin "1") (pinfunction "1_1") (pintype "input"))
      (node (ref "C28") (pin "1") (pinfunction "1_1") (pintype "input"))
      (node (ref "C29") (pin "2") (pinfunction "2_2") (pintype "input"))
      (node (ref "C3") (pin "2") (pinfunction "2_2") (pintype "input"))
      (node (ref "C35") (pin "2") (pinfunction "2_2") (pintype "input"))
      (node (ref "C4") (pin "1") (pinfunction "1_1") (pintype "input"))
      (node (ref "C5") (pin "1") (pinfunction "1_1") (pintype "input"))
      (node (ref "C6") (pin "1") (pinfunction "1_1") (pintype "input"))
      (node (ref "C7") (pin "2") (pinfunction "2_2") (pintype "input"))
      (node (ref "C8") (pin "1") (pinfunction "1_1") (pintype "input"))
      (node (ref "D3") (pin "2") (pinfunction "GND_2") (pintype "unspecified"))
      (node (ref "GND1") (pin "P$1") (pinfunction "1_P$1") (pintype "unspecified"))
      (node (ref "LED2") (pin "4") (pinfunction "GND_4") (pintype "unspecified"))
      (node (ref "LEDS") (pin "1") (pinfunction "1_1") (pintype "unspecified"))
      (node (ref "Q6") (pin "2") (pinfunction "S1_2") (pintype "unspecified"))
      (node (ref "Q6") (pin "3") (pinfunction "S1_3") (pintype "unspecified"))
      (node (ref "R25") (pin "2") (pinfunction "2_2") (pintype "input"))
      (node (ref "R26") (pin "2") (pinfunction "2_2") (pintype "input"))
      (node (ref "R29") (pin "1") (pinfunction "1_1") (pintype "input"))
      (node (ref "R56") (pin "1") (pinfunction "1_1") (pintype "input"))
      (node (ref "R57") (pin "2") (pinfunction "2_2") (pintype "input"))
      (node (ref "R60") (pin "1") (pinfunction "1_1") (pintype "input"))
      (node (ref "SJ12") (pin "1") (pinfunction "1_1") (pintype "unspecified"))
      (node (ref "SJ3") (pin "1") (pinfunction "1_1") (pintype "unspecified"))
      (node (ref "SJ4") (pin "1") (pinfunction "1_1") (pintype "unspecified"))
      (node (ref "SJ5") (pin "1") (pinfunction "1_1") (pintype "unspecified"))
      (node (ref "SJ6") (pin "1") (pinfunction "1_1") (pintype "unspecified"))
      (node (ref "SJ9") (pin "1") (pinfunction "1_1") (pintype "unspecified"))
      (node (ref "SW1") (pin "4") (pinfunction "4_4") (pintype "unspecified"))
      (node (ref "SW1") (pin "5") (pinfunction "5_5") (pintype "unspecified"))
      (node (ref "SW1") (pin "6") (pinfunction "6_6") (pintype "unspecified"))
      (node (ref "SW1") (pin "7") (pinfunction "7_7") (pintype "unspecified"))
      (node (ref "SW3") (pin "1") (pinfunction "A_1") (pintype "unspecified"))
      (node (ref "SW3") (pin "2") (pinfunction "B_2") (pintype "unspecified"))
      (node (ref "SW5") (pin "1") (pinfunction "A_1") (pintype "unspecified"))
      (node (ref "SW5") (pin "2") (pinfunction "B_2") (pintype "unspecified"))
      (node (ref "U1") (pin "5") (pinfunction "GND_5") (pintype "unspecified"))
      (node (ref "U1") (pin "9") (pinfunction "EP_9") (pintype "unspecified"))
      (node (ref "U2") (pin "2") (pinfunction "GND_2") (pintype "unspecified"))
      (node (ref "U3") (pin "29") (pinfunction "EP_29") (pintype "unspecified"))
      (node (ref "U3") (pin "3") (pinfunction "GND_3") (pintype "unspecified"))
      (node (ref "U5") (pin "11") (pinfunction "GND_11") (pintype "unspecified"))
      (node (ref "U5") (pin "15") (pinfunction "GND_15") (pintype "unspecified"))
      (node (ref "U5") (pin "17") (pinfunction "EP_17") (pintype "unspecified"))
      (node (ref "U5") (pin "3") (pinfunction "GND_3") (pintype "unspecified"))
      (node (ref "U6") (pin "1") (pinfunction "GND_1") (pintype "unspecified"))
      (node (ref "U6") (pin "15") (pinfunction "GND_15") (pintype "unspecified"))
      (node (ref "U6") (pin "38") (pinfunction "GND_38") (pintype "unspecified"))
      (node (ref "U6") (pin "39") (pinfunction "GND_39") (pintype "unspecified"))
      (node (ref "U7") (pin "11") (pinfunction "GND_11") (pintype "unspecified"))
      (node (ref "U7") (pin "15") (pinfunction "GND_15") (pintype "unspecified"))
      (node (ref "U7") (pin "17") (pinfunction "EP_17") (pintype "unspecified"))
      (node (ref "U7") (pin "3") (pinfunction "GND_3") (pintype "unspecified"))
      (node (ref "U8") (pin "1") (pinfunction "GND_1") (pintype "unspecified"))
      (node (ref "USB2") (pin "5") (pinfunction "GND_5") (pintype "unspecified"))
      (node (ref "USB2") (pin "6") (pinfunction "SH1_6") (pintype "unspecified"))
      (node (ref "USB2") (pin "7") (pinfunction "SH2_7") (pintype "unspecified"))
      (node (ref "USB2") (pin "8") (pinfunction "SH3_8") (pintype "unspecified"))
      (node (ref "USB2") (pin "9") (pinfunction "SH4_9") (pintype "unspecified"))
      (node (ref "W") (pin "2") (pinfunction "2_2") (pintype "input"))
    )
    (net (code "6") (name "GPIO0") (class "Default")
      (node (ref "BTN1") (pin "P$1") (pinfunction "1_P$1") (pintype "unspecified"))
      (node (ref "Q2") (pin "3") (pinfunction "C_3") (pintype "unspecified"))
      (node (ref "R21") (pin "2") (pinfunction "2_2") (pintype "input"))
      (node (ref "SW5") (pin "3") (pinfunction "C_3") (pintype "unspecified"))
      (node (ref "SW5") (pin "4") (pinfunction "D_4") (pintype "unspecified"))
      (node (ref "U6") (pin "25") (pinfunction "IO0_25") (pintype "unspecified"))
    )
    (net (code "7") (name "GPIO01") (class "Default")
      (node (ref "R12") (pin "1") (pinfunction "1_1") (pintype "input"))
      (node (ref "U6") (pin "35") (pinfunction "TXD0_35") (pintype "unspecified"))
    )
    (net (code "8") (name "GPIO02") (class "Default")
      (node (ref "BTN2") (pin "P$1") (pinfunction "1_P$1") (pintype "unspecified"))
      (node (ref "U6") (pin "24") (pinfunction "IO2_24") (pintype "unspecified"))
    )
    (net (code "9") (name "GPIO03") (class "Default")
      (node (ref "R13") (pin "1") (pinfunction "1_1") (pintype "input"))
      (node (ref "U6") (pin "34") (pinfunction "RXD0_34") (pintype "unspecified"))
    )
    (net (code "10") (name "GPIO04") (class "Default")
      (node (ref "BTN0") (pin "P$1") (pinfunction "1_P$1") (pintype "unspecified"))
      (node (ref "U6") (pin "26") (pinfunction "IO4_26") (pintype "unspecified"))
    )
    (net (code "11") (name "GPIO12") (class "Default")
      (node (ref "BTN5") (pin "P$1") (pinfunction "1_P$1") (pintype "unspecified"))
      (node (ref "U6") (pin "14") (pinfunction "IO12_14") (pintype "unspecified"))
    )
    (net (code "12") (name "GPIO13") (class "Default")
      (node (ref "BTN4") (pin "P$1") (pinfunction "1_P$1") (pintype "unspecified"))
      (node (ref "U6") (pin "16") (pinfunction "IO13_16") (pintype "unspecified"))
    )
    (net (code "13") (name "GPIO14") (class "Default")
      (node (ref "BTN6") (pin "P$1") (pinfunction "1_P$1") (pintype "unspecified"))
      (node (ref "U6") (pin "13") (pinfunction "IO14_13") (pintype "unspecified"))
    )
    (net (code "14") (name "GPIO15") (class "Default")
      (node (ref "BTN3") (pin "P$1") (pinfunction "1_P$1") (pintype "unspecified"))
      (node (ref "U6") (pin "23") (pinfunction "IO15_23") (pintype "unspecified"))
    )
    (net (code "15") (name "GPIO21") (class "Default")
      (node (ref "R28") (pin "2") (pinfunction "2_2") (pintype "input"))
      (node (ref "U1") (pin "3") (pinfunction "CHG#_3") (pintype "unspecified"))
      (node (ref "U6") (pin "33") (pinfunction "IO21_33") (pintype "unspecified"))
    )
    (net (code "16") (name "GPIO22") (class "Default")
      (node (ref "U5") (pin "1") (pinfunction "DIN_1") (pintype "unspecified"))
      (node (ref "U6") (pin "36") (pinfunction "IO22_36") (pintype "unspecified"))
      (node (ref "U7") (pin "1") (pinfunction "DIN_1") (pintype "unspecified"))
    )
    (net (code "17") (name "GPIO25") (class "Default")
      (node (ref "U5") (pin "14") (pinfunction "LRCLK_14") (pintype "unspecified"))
      (node (ref "U6") (pin "10") (pinfunction "IO25_10") (pintype "unspecified"))
      (node (ref "U7") (pin "14") (pinfunction "LRCLK_14") (pintype "unspecified"))
    )
    (net (code "18") (name "GPIO26") (class "Default")
      (node (ref "U5") (pin "16") (pinfunction "BCLK_16") (pintype "unspecified"))
      (node (ref "U6") (pin "11") (pinfunction "IO26_11") (pintype "unspecified"))
      (node (ref "U7") (pin "16") (pinfunction "BCLK_16") (pintype "unspecified"))
    )
    (net (code "19") (name "GPIO27") (class "Default")
      (node (ref "BTN7") (pin "P$1") (pinfunction "1_P$1") (pintype "unspecified"))
      (node (ref "U6") (pin "12") (pinfunction "IO27_12") (pintype "unspecified"))
    )
    (net (code "20") (name "GPIO32") (class "Default")
      (node (ref "BTN9") (pin "P$1") (pinfunction "1_P$1") (pintype "unspecified"))
      (node (ref "U6") (pin "8") (pinfunction "IO32_8") (pintype "unspecified"))
    )
    (net (code "21") (name "GPIO33") (class "Default")
      (node (ref "BTN8") (pin "P$1") (pinfunction "1_P$1") (pintype "unspecified"))
      (node (ref "R39") (pin "2") (pinfunction "2_2") (pintype "input"))
      (node (ref "U6") (pin "9") (pinfunction "IO33_9") (pintype "unspecified"))
    )
    (net (code "22") (name "GPIO34") (class "Default")
      (node (ref "C8") (pin "2") (pinfunction "2_2") (pintype "input"))
      (node (ref "R60") (pin "2") (pinfunction "2_2") (pintype "input"))
      (node (ref "R61") (pin "1") (pinfunction "1_1") (pintype "input"))
      (node (ref "U6") (pin "6") (pinfunction "IO34_6") (pintype "unspecified"))
    )
    (net (code "23") (name "MCU_RST") (class "Default")
      (node (ref "C3") (pin "1") (pinfunction "1_1") (pintype "input"))
      (node (ref "Q1") (pin "3") (pinfunction "C_3") (pintype "unspecified"))
      (node (ref "R2") (pin "2") (pinfunction "2_2") (pintype "input"))
      (node (ref "SW3") (pin "3") (pinfunction "C_3") (pintype "unspecified"))
      (node (ref "SW3") (pin "4") (pinfunction "D_4") (pintype "unspecified"))
      (node (ref "U6") (pin "3") (pinfunction "EN_3") (pintype "unspecified"))
    )
    (net (code "24") (name "MCU_RX") (class "Default")
      (node (ref "R13") (pin "2") (pinfunction "2_2") (pintype "input"))
      (node (ref "U3") (pin "26") (pinfunction "TXD_26") (pintype "unspecified"))
    )
    (net (code "25") (name "MCU_TX") (class "Default")
      (node (ref "R12") (pin "2") (pinfunction "2_2") (pintype "input"))
      (node (ref "U3") (pin "25") (pinfunction "RXD_25") (pintype "unspecified"))
    )
    (net (code "26") (name "Net-(D1-K)") (class "Default")
      (node (ref "D1") (pin "1") (pinfunction "K_1") (pintype "unspecified"))
      (node (ref "EXT_SW_1") (pin "P$1") (pinfunction "1_P$1") (pintype "unspecified"))
      (node (ref "J5") (pin "2") (pinfunction "2_2") (pintype "unspecified"))
      (node (ref "Q3") (pin "2") (pinfunction "S_2") (pintype "unspecified"))
      (node (ref "SW1") (pin "1") (pinfunction "1_1") (pintype "unspecified"))
    )
    (net (code "27") (name "Net-(D2-+)") (class "Default")
      (node (ref "D2") (pin "2") (pinfunction "+_2") (pintype "unspecified"))
      (node (ref "L6") (pin "2") (pinfunction "2_2") (pintype "unspecified"))
      (node (ref "U2") (pin "1") (pinfunction "SW_1") (pintype "unspecified"))
    )
    (net (code "28") (name "Net-(LED2-DI)") (class "Default")
      (node (ref "LED2") (pin "1") (pinfunction "DI_1") (pintype "unspecified"))
      (node (ref "R39") (pin "1") (pinfunction "1_1") (pintype "input"))
    )
    (net (code "29") (name "Net-(LED2-DO)") (class "Default")
      (node (ref "LED2") (pin "3") (pinfunction "DO_3") (pintype "unspecified"))
      (node (ref "LEDS") (pin "2") (pinfunction "2_2") (pintype "unspecified"))
    )
    (net (code "30") (name "Net-(LED25-C)") (class "Default")
      (node (ref "LED25") (pin "2") (pinfunction "C_2") (pintype "input"))
      (node (ref "R28") (pin "1") (pinfunction "1_1") (pintype "input"))
    )
    (net (code "31") (name "Net-(LED29-K)") (class "Default")
      (node (ref "LED29") (pin "2") (pinfunction "K_2") (pintype "unspecified"))
      (node (ref "R27") (pin "1") (pinfunction "1_1") (pintype "input"))
    )
    (net (code "32") (name "Net-(Q1-B)") (class "Default")
      (node (ref "Q1") (pin "1") (pinfunction "B_1") (pintype "unspecified"))
      (node (ref "R3") (pin "2") (pinfunction "2_2") (pintype "input"))
    )
    (net (code "33") (name "Net-(Q2-B)") (class "Default")
      (node (ref "Q2") (pin "1") (pinfunction "B_1") (pintype "unspecified"))
      (node (ref "R9") (pin "2") (pinfunction "2_2") (pintype "input"))
    )
    (net (code "34") (name "Net-(Q5-CS)") (class "Default")
      (node (ref "Q5") (pin "2") (pinfunction "CS_2") (pintype "unspecified"))
      (node (ref "R57") (pin "1") (pinfunction "1_1") (pintype "input"))
    )
    (net (code "35") (name "Net-(Q5-OC)") (class "Default")
      (node (ref "Q5") (pin "3") (pinfunction "OC_3") (pintype "unspecified"))
      (node (ref "Q6") (pin "4") (pinfunction "G1_4") (pintype "unspecified"))
    )
    (net (code "36") (name "Net-(Q5-OD)") (class "Default")
      (node (ref "Q5") (pin "1") (pinfunction "OD_1") (pintype "unspecified"))
      (node (ref "Q6") (pin "5") (pinfunction "G2_5") (pintype "unspecified"))
    )
    (net (code "37") (name "Net-(Q5-VCC)") (class "Default")
      (node (ref "C34") (pin "2") (pinfunction "2_2") (pintype "input"))
      (node (ref "Q5") (pin "5") (pinfunction "VCC_5") (pintype "unspecified"))
      (node (ref "R58") (pin "2") (pinfunction "2_2") (pintype "input"))
    )
    (net (code "38") (name "Net-(Q6-D12-Pad1)") (class "Default")
      (node (ref "Q6") (pin "1") (pinfunction "D12_1") (pintype "unspecified"))
      (node (ref "Q6") (pin "8") (pinfunction "D12_8") (pintype "unspecified"))
    )
    (net (code "39") (name "Net-(R1-Pad2)") (class "Default")
      (node (ref "R1") (pin "2") (pinfunction "2_2") (pintype "input"))
      (node (ref "SJ11") (pin "1") (pinfunction "1_1") (pintype "unspecified"))
    )
    (net (code "40") (name "Net-(R5-Pad1)") (class "Default")
      (node (ref "R5") (pin "1") (pinfunction "1_1") (pintype "input"))
      (node (ref "SJ12") (pin "2") (pinfunction "2_2") (pintype "unspecified"))
    )
    (net (code "41") (name "Net-(R6-Pad2)") (class "Default")
      (node (ref "R6") (pin "2") (pinfunction "2_2") (pintype "input"))
      (node (ref "SJ8") (pin "1") (pinfunction "1_1") (pintype "unspecified"))
    )
    (net (code "42") (name "Net-(R40-Pad1)") (class "Default")
      (node (ref "R40") (pin "1") (pinfunction "1_1") (pintype "input"))
      (node (ref "SJ6") (pin "2") (pinfunction "2_2") (pintype "unspecified"))
    )
    (net (code "43") (name "Net-(R41-Pad2)") (class "Default")
      (node (ref "R41") (pin "2") (pinfunction "2_2") (pintype "input"))
      (node (ref "SJ2") (pin "1") (pinfunction "1_1") (pintype "unspecified"))
    )
    (net (code "44") (name "Net-(R63-Pad2)") (class "Default")
      (node (ref "R63") (pin "2") (pinfunction "2_2") (pintype "input"))
      (node (ref "SJ4") (pin "2") (pinfunction "2_2") (pintype "unspecified"))
    )
    (net (code "45") (name "Net-(U1-IMIN)") (class "Default")
      (node (ref "R25") (pin "1") (pinfunction "1_1") (pintype "input"))
      (node (ref "U1") (pin "6") (pinfunction "IMIN_6") (pintype "unspecified"))
    )
    (net (code "46") (name "Net-(U1-IREF)") (class "Default")
      (node (ref "R26") (pin "1") (pinfunction "1_1") (pintype "input"))
      (node (ref "R63") (pin "1") (pinfunction "1_1") (pintype "input"))
      (node (ref "U1") (pin "7") (pinfunction "IREF_7") (pintype "unspecified"))
    )
    (net (code "47") (name "Net-(U1-PPR#)") (class "Default")
      (node (ref "R27") (pin "2") (pinfunction "2_2") (pintype "input"))
      (node (ref "U1") (pin "2") (pinfunction "PPR#_2") (pintype "unspecified"))
    )
    (net (code "48") (name "Net-(U2-FB)") (class "Default")
      (node (ref "R16") (pin "1") (pinfunction "1_1") (pintype "input"))
      (node (ref "R56") (pin "2") (pinfunction "2_2") (pintype "input"))
      (node (ref "U2") (pin "3") (pinfunction "FB_3") (pintype "unspecified"))
    )
    (net (code "49") (name "Net-(U3-D+)") (class "Default")
      (node (ref "D3") (pin "6") (pinfunction "IO1_6") (pintype "unspecified"))
      (node (ref "U3") (pin "4") (pinfunction "D+_4") (pintype "unspecified"))
    )
    (net (code "50") (name "Net-(U3-D-)") (class "Default")
      (node (ref "D3") (pin "4") (pinfunction "IO2_4") (pintype "unspecified"))
      (node (ref "U3") (pin "5") (pinfunction "D-_5") (pintype "unspecified"))
    )
    (net (code "51") (name "Net-(U5-GAIN_SLOT)") (class "Default")
      (node (ref "R40") (pin "2") (pinfunction "2_2") (pintype "input"))
      (node (ref "R41") (pin "1") (pinfunction "1_1") (pintype "input"))
      (node (ref "SJ5") (pin "2") (pinfunction "2_2") (pintype "unspecified"))
      (node (ref "SJ7") (pin "1") (pinfunction "1_1") (pintype "unspecified"))
      (node (ref "U5") (pin "2") (pinfunction "GAIN_SLOT_2") (pintype "unspecified"))
    )
    (net (code "52") (name "Net-(U5-OUTN)") (class "Default")
      (node (ref "U12") (pin "2") (pinfunction "2_2") (pintype "unspecified"))
      (node (ref "U5") (pin "10") (pinfunction "OUTN_10") (pintype "unspecified"))
    )
    (net (code "53") (name "Net-(U5-OUTP)") (class "Default")
      (node (ref "U12") (pin "1") (pinfunction "1_1") (pintype "unspecified"))
      (node (ref "U5") (pin "9") (pinfunction "OUTP_9") (pintype "unspecified"))
    )
    (net (code "54") (name "Net-(U5-SD_MODE#)") (class "Default")
      (node (ref "R4") (pin "1") (pinfunction "1_1") (pintype "input"))
      (node (ref "SJ1") (pin "1") (pinfunction "1_1") (pintype "unspecified"))
      (node (ref "U5") (pin "4") (pinfunction "SD_MODE#_4") (pintype "unspecified"))
    )
    (net (code "55") (name "Net-(U7-GAIN_SLOT)") (class "Default")
      (node (ref "R5") (pin "2") (pinfunction "2_2") (pintype "input"))
      (node (ref "R6") (pin "1") (pinfunction "1_1") (pintype "input"))
      (node (ref "SJ10") (pin "1") (pinfunction "1_1") (pintype "unspecified"))
      (node (ref "SJ9") (pin "2") (pinfunction "2_2") (pintype "unspecified"))
      (node (ref "U7") (pin "2") (pinfunction "GAIN_SLOT_2") (pintype "unspecified"))
    )
    (net (code "56") (name "Net-(U7-OUTN)") (class "Default")
      (node (ref "U13") (pin "2") (pinfunction "2_2") (pintype "unspecified"))
      (node (ref "U7") (pin "10") (pinfunction "OUTN_10") (pintype "unspecified"))
    )
    (net (code "57") (name "Net-(U7-OUTP)") (class "Default")
      (node (ref "U13") (pin "1") (pinfunction "1_1") (pintype "unspecified"))
      (node (ref "U7") (pin "9") (pinfunction "OUTP_9") (pintype "unspecified"))
    )
    (net (code "58") (name "Net-(U7-SD_MODE#)") (class "Default")
      (node (ref "R1") (pin "1") (pinfunction "1_1") (pintype "input"))
      (node (ref "R10") (pin "1") (pinfunction "1_1") (pintype "input"))
      (node (ref "U7") (pin "4") (pinfunction "SD_MODE#_4") (pintype "unspecified"))
    )
    (net (code "59") (name "RTS") (class "Default")
      (node (ref "Q1") (pin "2") (pinfunction "E_2") (pintype "unspecified"))
      (node (ref "R9") (pin "1") (pinfunction "1_1") (pintype "input"))
      (node (ref "U3") (pin "24") (pinfunction "RTS_24") (pintype "unspecified"))
    )
    (net (code "60") (name "USBM") (class "Default")
      (node (ref "D3") (pin "3") (pinfunction "IO2_3") (pintype "unspecified"))
      (node (ref "USB2") (pin "2") (pinfunction "D-_2") (pintype "unspecified"))
    )
    (net (code "61") (name "USBP") (class "Default")
      (node (ref "D3") (pin "1") (pinfunction "IO1_1") (pintype "unspecified"))
      (node (ref "USB2") (pin "3") (pinfunction "D+_3") (pintype "unspecified"))
    )
    (net (code "62") (name "VBAT") (class "Default")
      (node (ref "BATT1") (pin "2") (pinfunction "2_2") (pintype "unspecified"))
      (node (ref "BT1") (pin "1") (pinfunction "+_1") (pintype "passive"))
      (node (ref "BT2") (pin "1") (pinfunction "+_1") (pintype "passive"))
      (node (ref "C20") (pin "2") (pinfunction "2_2") (pintype "input"))
      (node (ref "LED29") (pin "1") (pinfunction "A_1") (pintype "unspecified"))
      (node (ref "Q3") (pin "3") (pinfunction "D_3") (pintype "unspecified"))
      (node (ref "R58") (pin "1") (pinfunction "1_1") (pintype "input"))
      (node (ref "R61") (pin "2") (pinfunction "2_2") (pintype "input"))
      (node (ref "U1") (pin "8") (pinfunction "BAT_8") (pintype "unspecified"))
      (node (ref "VBAT1") (pin "P$1") (pinfunction "1_P$1") (pintype "unspecified"))
    )
    (net (code "63") (name "VBUS") (class "Default")
      (node (ref "C11") (pin "2") (pinfunction "2_2") (pintype "input"))
      (node (ref "C18") (pin "2") (pinfunction "2_2") (pintype "input"))
      (node (ref "C19") (pin "2") (pinfunction "2_2") (pintype "input"))
      (node (ref "C28") (pin "2") (pinfunction "2_2") (pintype "input"))
      (node (ref "C35") (pin "1") (pinfunction "1_1") (pintype "input"))
      (node (ref "EXT_SW_2") (pin "P$1") (pinfunction "1_P$1") (pintype "unspecified"))
      (node (ref "J5") (pin "1") (pinfunction "1_1") (pintype "unspecified"))
      (node (ref "L6") (pin "1") (pinfunction "1_1") (pintype "unspecified"))
      (node (ref "LED2") (pin "2") (pinfunction "VDD_2") (pintype "unspecified"))
      (node (ref "LEDS") (pin "3") (pinfunction "3_3") (pintype "unspecified"))
      (node (ref "SW1") (pin "2") (pinfunction "2_2") (pintype "unspecified"))
      (node (ref "U2") (pin "4") (pinfunction "EN_4") (pintype "unspecified"))
      (node (ref "U2") (pin "5") (pinfunction "VIN_5") (pintype "unspecified"))
      (node (ref "U8") (pin "2") (pinfunction "VIN_2") (pintype "unspecified"))
      (node (ref "VBUS1") (pin "P$1") (pinfunction "1_P$1") (pintype "unspecified"))
    )
    (net (code "64") (name "VUSB") (class "Default")
      (node (ref "C21") (pin "2") (pinfunction "2_2") (pintype "input"))
      (node (ref "C4") (pin "2") (pinfunction "2_2") (pintype "input"))
      (node (ref "C5") (pin "2") (pinfunction "2_2") (pintype "input"))
      (node (ref "D1") (pin "2") (pinfunction "A_2") (pintype "unspecified"))
      (node (ref "D3") (pin "5") (pinfunction "VBUS_5") (pintype "unspecified"))
      (node (ref "Q3") (pin "1") (pinfunction "G_1") (pintype "unspecified"))
      (node (ref "R29") (pin "2") (pinfunction "2_2") (pintype "input"))
      (node (ref "U1") (pin "1") (pinfunction "VIN_1") (pintype "unspecified"))
      (node (ref "U3") (pin "8") (pinfunction "VBUS_8") (pintype "unspecified"))
      (node (ref "USB2") (pin "1") (pinfunction "VBUS_1") (pintype "unspecified"))
      (node (ref "VUSB") (pin "P$1") (pinfunction "1_P$1") (pintype "unspecified"))
    )
    (net (code "65") (name "unconnected-(Q5-TD-Pad4)") (class "Default")
      (node (ref "Q5") (pin "4") (pinfunction "TD_4") (pintype "unspecified+no_connect"))
    )
    (net (code "66") (name "unconnected-(SW1-Pad3)") (class "Default")
      (node (ref "SW1") (pin "3") (pinfunction "3_3") (pintype "unspecified+no_connect"))
    )
    (net (code "67") (name "unconnected-(U1-EN#-Pad4)") (class "Default")
      (node (ref "U1") (pin "4") (pinfunction "EN#_4") (pintype "unspecified+no_connect"))
    )
    (net (code "68") (name "unconnected-(U2-OC-Pad6)") (class "Default")
      (node (ref "U2") (pin "6") (pinfunction "OC_6") (pintype "unspecified+no_connect"))
    )
    (net (code "69") (name "unconnected-(U3-CTS-Pad23)") (class "Default")
      (node (ref "U3") (pin "23") (pinfunction "CTS_23") (pintype "unspecified+no_connect"))
    )
    (net (code "70") (name "unconnected-(U3-DCD-Pad1)") (class "Default")
      (node (ref "U3") (pin "1") (pinfunction "DCD_1") (pintype "unspecified+no_connect"))
    )
    (net (code "71") (name "unconnected-(U3-DSR-Pad27)") (class "Default")
      (node (ref "U3") (pin "27") (pinfunction "DSR_27") (pintype "unspecified+no_connect"))
    )
    (net (code "72") (name "unconnected-(U3-NC-Pad10)") (class "Default")
      (node (ref "U3") (pin "10") (pinfunction "NC_10") (pintype "unspecified+no_connect"))
    )
    (net (code "73") (name "unconnected-(U3-NC-Pad13)") (class "Default")
      (node (ref "U3") (pin "13") (pinfunction "NC_13") (pintype "unspecified+no_connect"))
    )
    (net (code "74") (name "unconnected-(U3-NC-Pad14)") (class "Default")
      (node (ref "U3") (pin "14") (pinfunction "NC_14") (pintype "unspecified+no_connect"))
    )
    (net (code "75") (name "unconnected-(U3-NC-Pad15)") (class "Default")
      (node (ref "U3") (pin "15") (pinfunction "NC_15") (pintype "unspecified+no_connect"))
    )
    (net (code "76") (name "unconnected-(U3-NC-Pad16)") (class "Default")
      (node (ref "U3") (pin "16") (pinfunction "NC_16") (pintype "unspecified+no_connect"))
    )
    (net (code "77") (name "unconnected-(U3-NC-Pad17)") (class "Default")
      (node (ref "U3") (pin "17") (pinfunction "NC_17") (pintype "unspecified+no_connect"))
    )
    (net (code "78") (name "unconnected-(U3-NC-Pad18)") (class "Default")
      (node (ref "U3") (pin "18") (pinfunction "NC_18") (pintype "unspecified+no_connect"))
    )
    (net (code "79") (name "unconnected-(U3-NC-Pad19)") (class "Default")
      (node (ref "U3") (pin "19") (pinfunction "NC_19") (pintype "unspecified+no_connect"))
    )
    (net (code "80") (name "unconnected-(U3-NC-Pad20)") (class "Default")
      (node (ref "U3") (pin "20") (pinfunction "NC_20") (pintype "unspecified+no_connect"))
    )
    (net (code "81") (name "unconnected-(U3-NC-Pad21)") (class "Default")
      (node (ref "U3") (pin "21") (pinfunction "NC_21") (pintype "unspecified+no_connect"))
    )
    (net (code "82") (name "unconnected-(U3-NC-Pad22)") (class "Default")
      (node (ref "U3") (pin "22") (pinfunction "NC_22") (pintype "unspecified+no_connect"))
    )
    (net (code "83") (name "unconnected-(U3-RI-Pad2)") (class "Default")
      (node (ref "U3") (pin "2") (pinfunction "RI_2") (pintype "unspecified+no_connect"))
    )
    (net (code "84") (name "unconnected-(U3-RST#-Pad9)") (class "Default")
      (node (ref "U3") (pin "9") (pinfunction "RST#_9") (pintype "unspecified+no_connect"))
    )
    (net (code "85") (name "unconnected-(U3-SUSPEND#-Pad11)") (class "Default")
      (node (ref "U3") (pin "11") (pinfunction "SUSPEND#_11") (pintype "unspecified+no_connect"))
    )
    (net (code "86") (name "unconnected-(U3-SUSPEND-Pad12)") (class "Default")
      (node (ref "U3") (pin "12") (pinfunction "SUSPEND_12") (pintype "unspecified+no_connect"))
    )
    (net (code "87") (name "unconnected-(U5-N.C.-Pad5)") (class "Default")
      (node (ref "U5") (pin "5") (pinfunction "N.C._5") (pintype "unspecified+no_connect"))
    )
    (net (code "88") (name "unconnected-(U5-N.C.-Pad6)") (class "Default")
      (node (ref "U5") (pin "6") (pinfunction "N.C._6") (pintype "unspecified+no_connect"))
    )
    (net (code "89") (name "unconnected-(U5-N.C.-Pad12)") (class "Default")
      (node (ref "U5") (pin "12") (pinfunction "N.C._12") (pintype "unspecified+no_connect"))
    )
    (net (code "90") (name "unconnected-(U5-N.C.-Pad13)") (class "Default")
      (node (ref "U5") (pin "13") (pinfunction "N.C._13") (pintype "unspecified+no_connect"))
    )
    (net (code "91") (name "unconnected-(U6-CLK-Pad20)") (class "Default")
      (node (ref "U6") (pin "20") (pinfunction "CLK_20") (pintype "unspecified+no_connect"))
    )
    (net (code "92") (name "unconnected-(U6-CMD-Pad19)") (class "Default")
      (node (ref "U6") (pin "19") (pinfunction "CMD_19") (pintype "unspecified+no_connect"))
    )
    (net (code "93") (name "unconnected-(U6-IO5-Pad29)") (class "Default")
      (node (ref "U6") (pin "29") (pinfunction "IO5_29") (pintype "unspecified+no_connect"))
    )
    (net (code "94") (name "unconnected-(U6-IO18-Pad30)") (class "Default")
      (node (ref "U6") (pin "30") (pinfunction "IO18_30") (pintype "unspecified+no_connect"))
    )
    (net (code "95") (name "unconnected-(U6-IO19-Pad31)") (class "Default")
      (node (ref "U6") (pin "31") (pinfunction "IO19_31") (pintype "unspecified+no_connect"))
    )
    (net (code "96") (name "unconnected-(U6-IO23-Pad37)") (class "Default")
      (node (ref "U6") (pin "37") (pinfunction "IO23_37") (pintype "unspecified+no_connect"))
    )
    (net (code "97") (name "unconnected-(U6-IO35-Pad7)") (class "Default")
      (node (ref "U6") (pin "7") (pinfunction "IO35_7") (pintype "unspecified+no_connect"))
    )
    (net (code "98") (name "unconnected-(U6-NC-Pad27)") (class "Default")
      (node (ref "U6") (pin "27") (pinfunction "NC_27") (pintype "unspecified+no_connect"))
    )
    (net (code "99") (name "unconnected-(U6-NC-Pad28)") (class "Default")
      (node (ref "U6") (pin "28") (pinfunction "NC_28") (pintype "unspecified+no_connect"))
    )
    (net (code "100") (name "unconnected-(U6-NC-Pad32)") (class "Default")
      (node (ref "U6") (pin "32") (pinfunction "NC_32") (pintype "unspecified+no_connect"))
    )
    (net (code "101") (name "unconnected-(U6-SD0-Pad21)") (class "Default")
      (node (ref "U6") (pin "21") (pinfunction "SD0_21") (pintype "unspecified+no_connect"))
    )
    (net (code "102") (name "unconnected-(U6-SD1-Pad22)") (class "Default")
      (node (ref "U6") (pin "22") (pinfunction "SD1_22") (pintype "unspecified+no_connect"))
    )
    (net (code "103") (name "unconnected-(U6-SD2-Pad17)") (class "Default")
      (node (ref "U6") (pin "17") (pinfunction "SD2_17") (pintype "unspecified+no_connect"))
    )
    (net (code "104") (name "unconnected-(U6-SD3-Pad18)") (class "Default")
      (node (ref "U6") (pin "18") (pinfunction "SD3_18") (pintype "unspecified+no_connect"))
    )
    (net (code "105") (name "unconnected-(U6-SENSOR_VN-Pad5)") (class "Default")
      (node (ref "U6") (pin "5") (pinfunction "SENSOR_VN_5") (pintype "unspecified+no_connect"))
    )
    (net (code "106") (name "unconnected-(U6-SENSOR_VP-Pad4)") (class "Default")
      (node (ref "U6") (pin "4") (pinfunction "SENSOR_VP_4") (pintype "unspecified+no_connect"))
    )
    (net (code "107") (name "unconnected-(U7-N.C.-Pad5)") (class "Default")
      (node (ref "U7") (pin "5") (pinfunction "N.C._5") (pintype "unspecified+no_connect"))
    )
    (net (code "108") (name "unconnected-(U7-N.C.-Pad6)") (class "Default")
      (node (ref "U7") (pin "6") (pinfunction "N.C._6") (pintype "unspecified+no_connect"))
    )
    (net (code "109") (name "unconnected-(U7-N.C.-Pad12)") (class "Default")
      (node (ref "U7") (pin "12") (pinfunction "N.C._12") (pintype "unspecified+no_connect"))
    )
    (net (code "110") (name "unconnected-(U7-N.C.-Pad13)") (class "Default")
      (node (ref "U7") (pin "13") (pinfunction "N.C._13") (pintype "unspecified+no_connect"))
    )
    (net (code "111") (name "unconnected-(USB2-ID-Pad4)") (class "Default")
      (node (ref "USB2") (pin "4") (pinfunction "ID_4") (pintype "unspecified+no_connect"))
    )
  )
)
